# EEG_ECG.net
KiCad netlist of a schematic drawn in Altium Designer
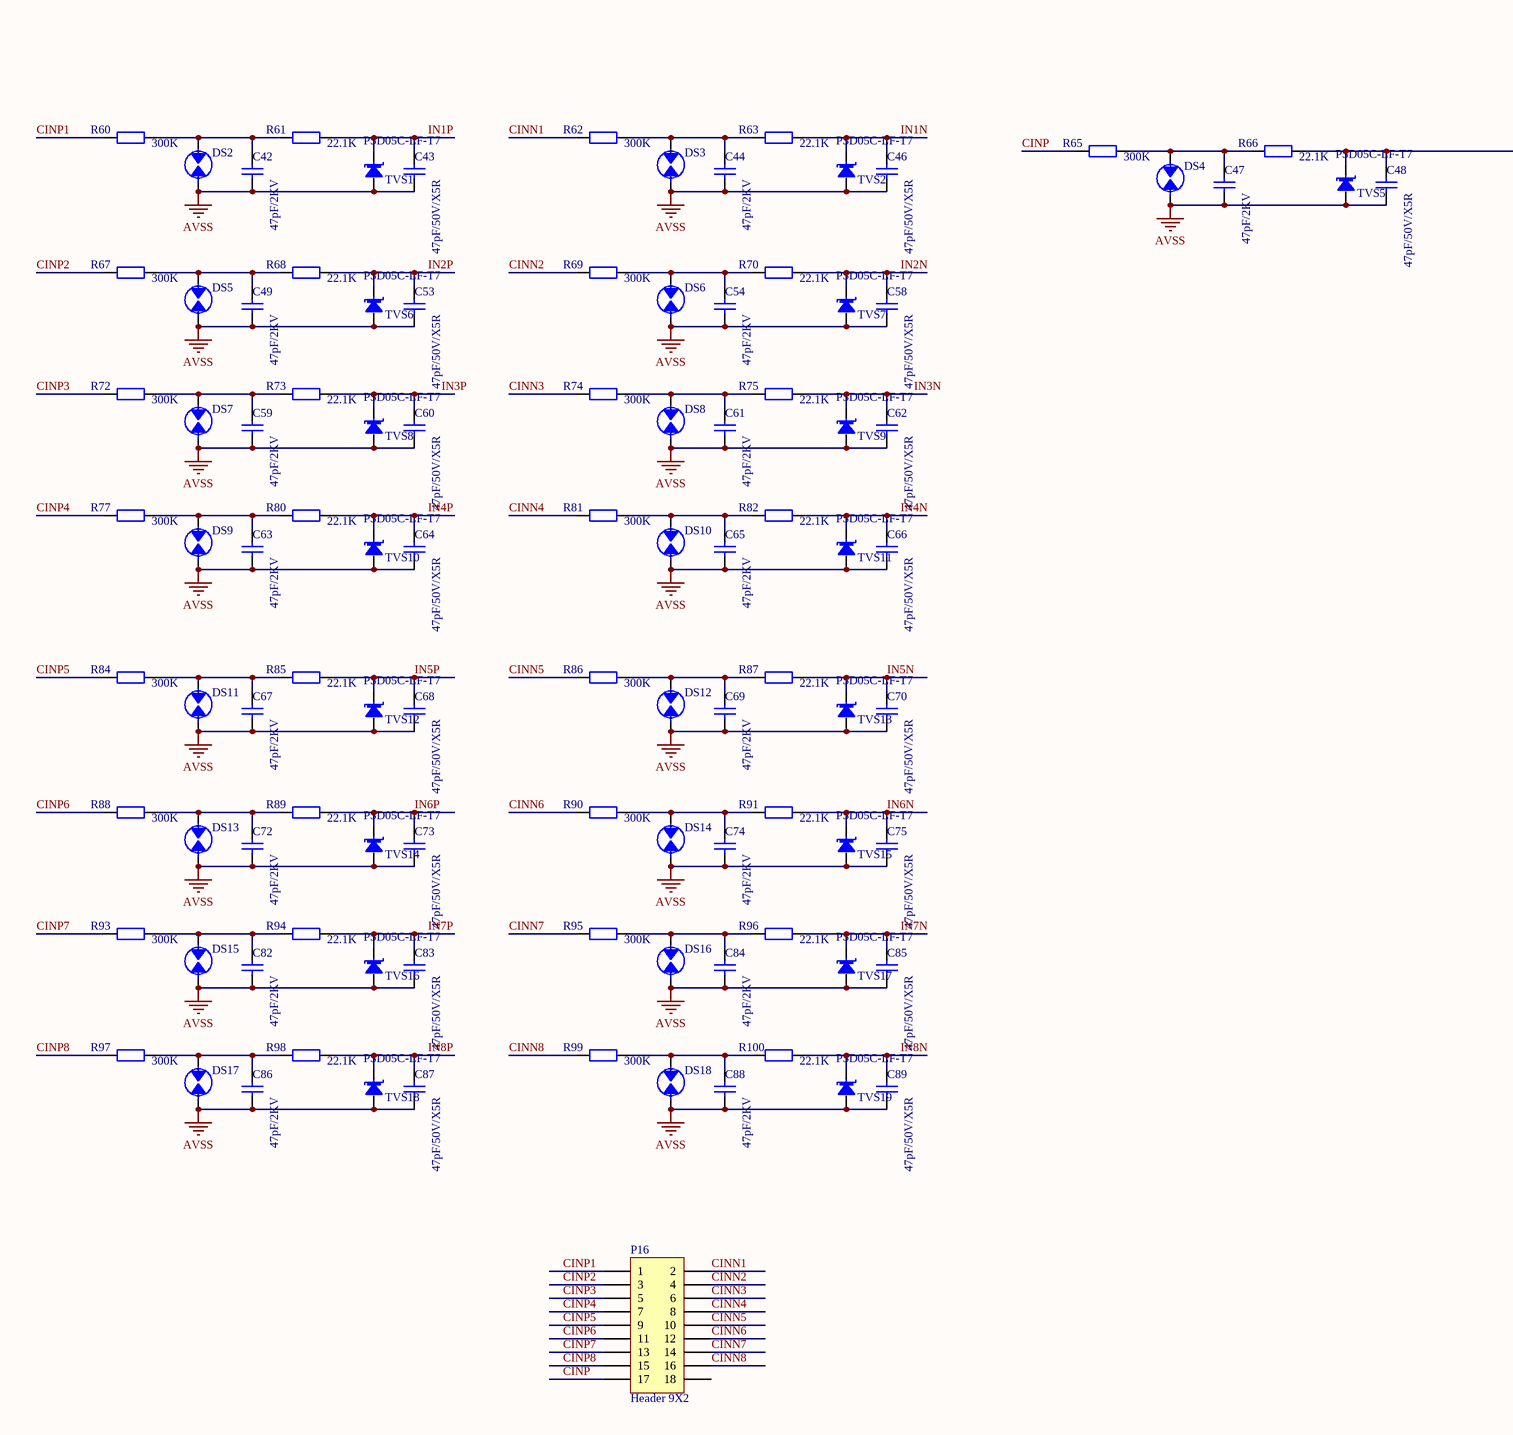
[diagram p0: EEG&ECG.SchDoc, top left]
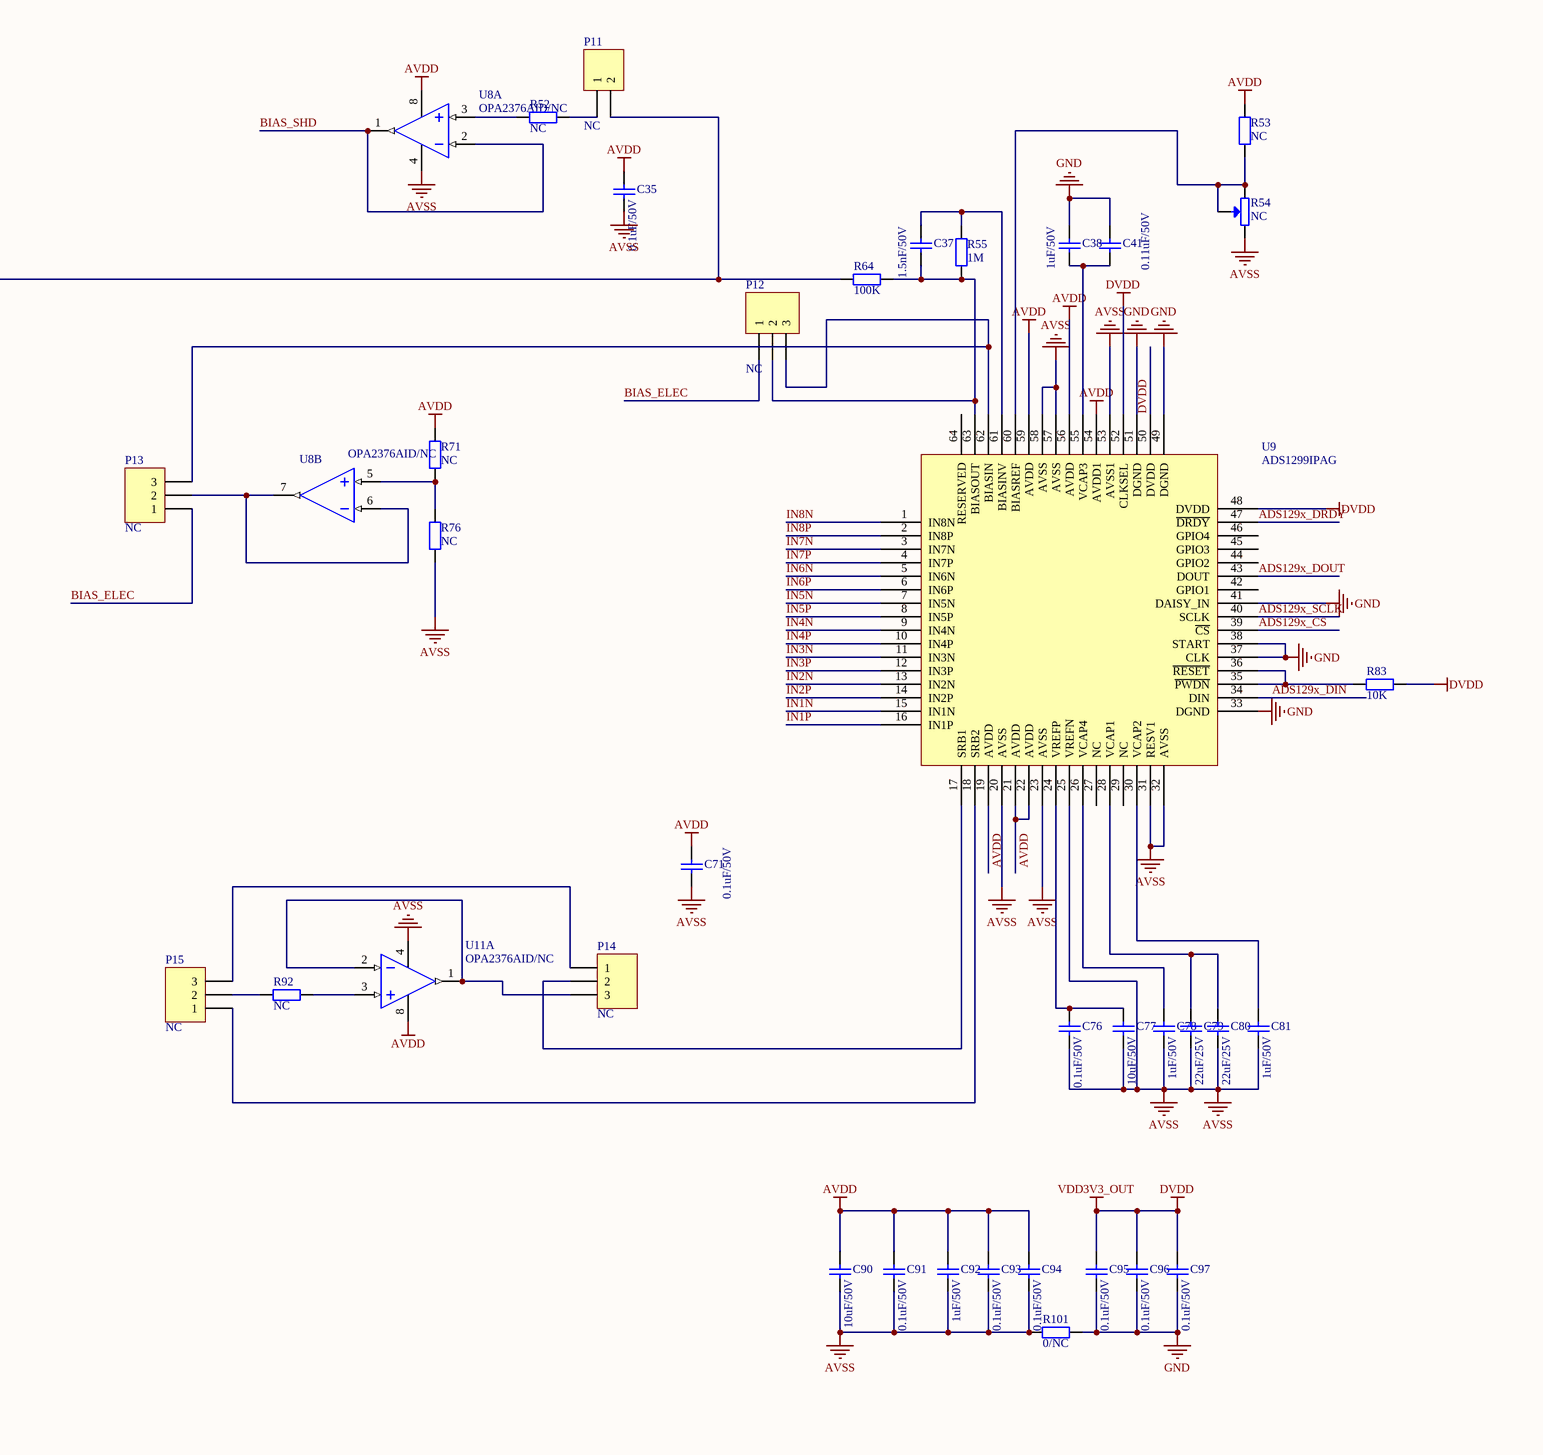
[diagram p1: EEG&ECG.SchDoc, top right]
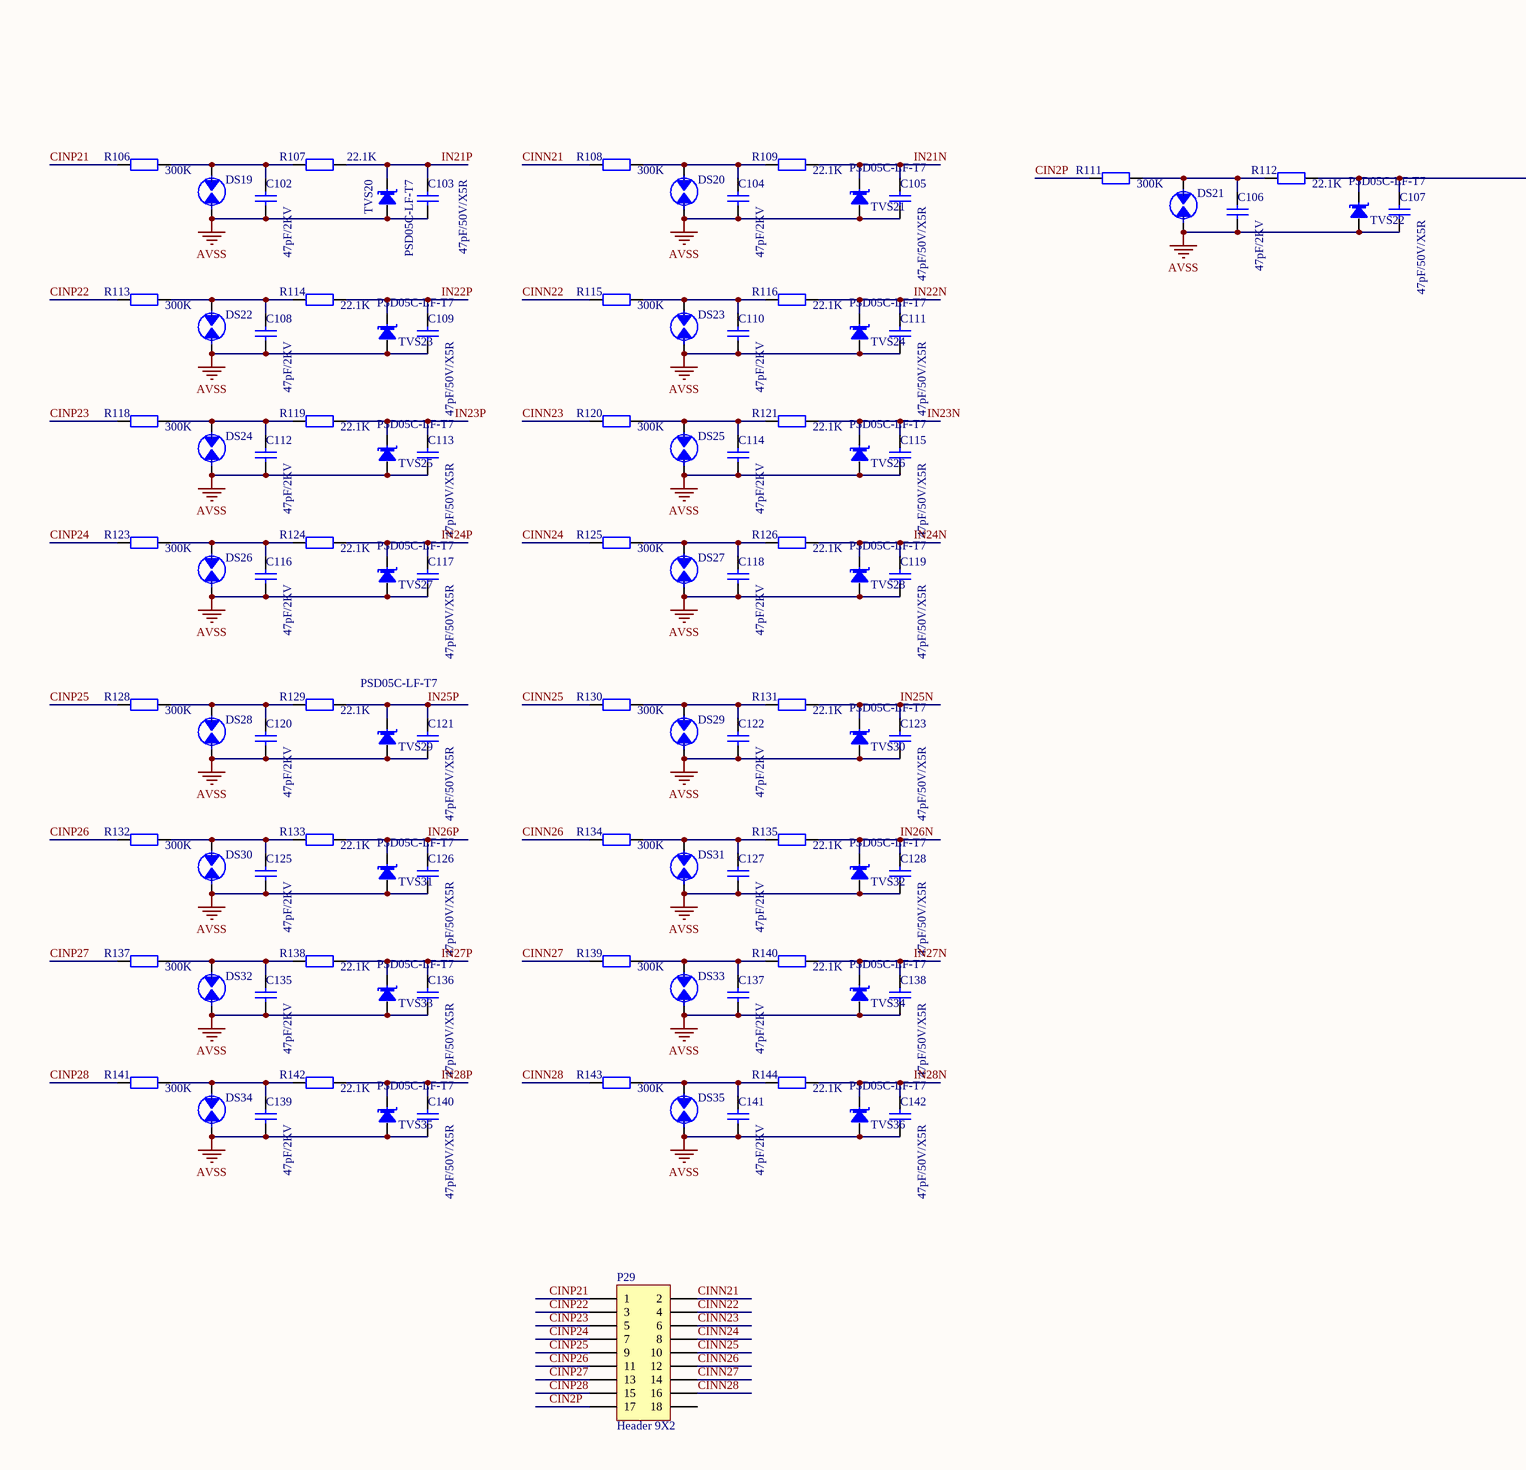
[diagram p2: EEG&ECG.SchDoc, bottom left]
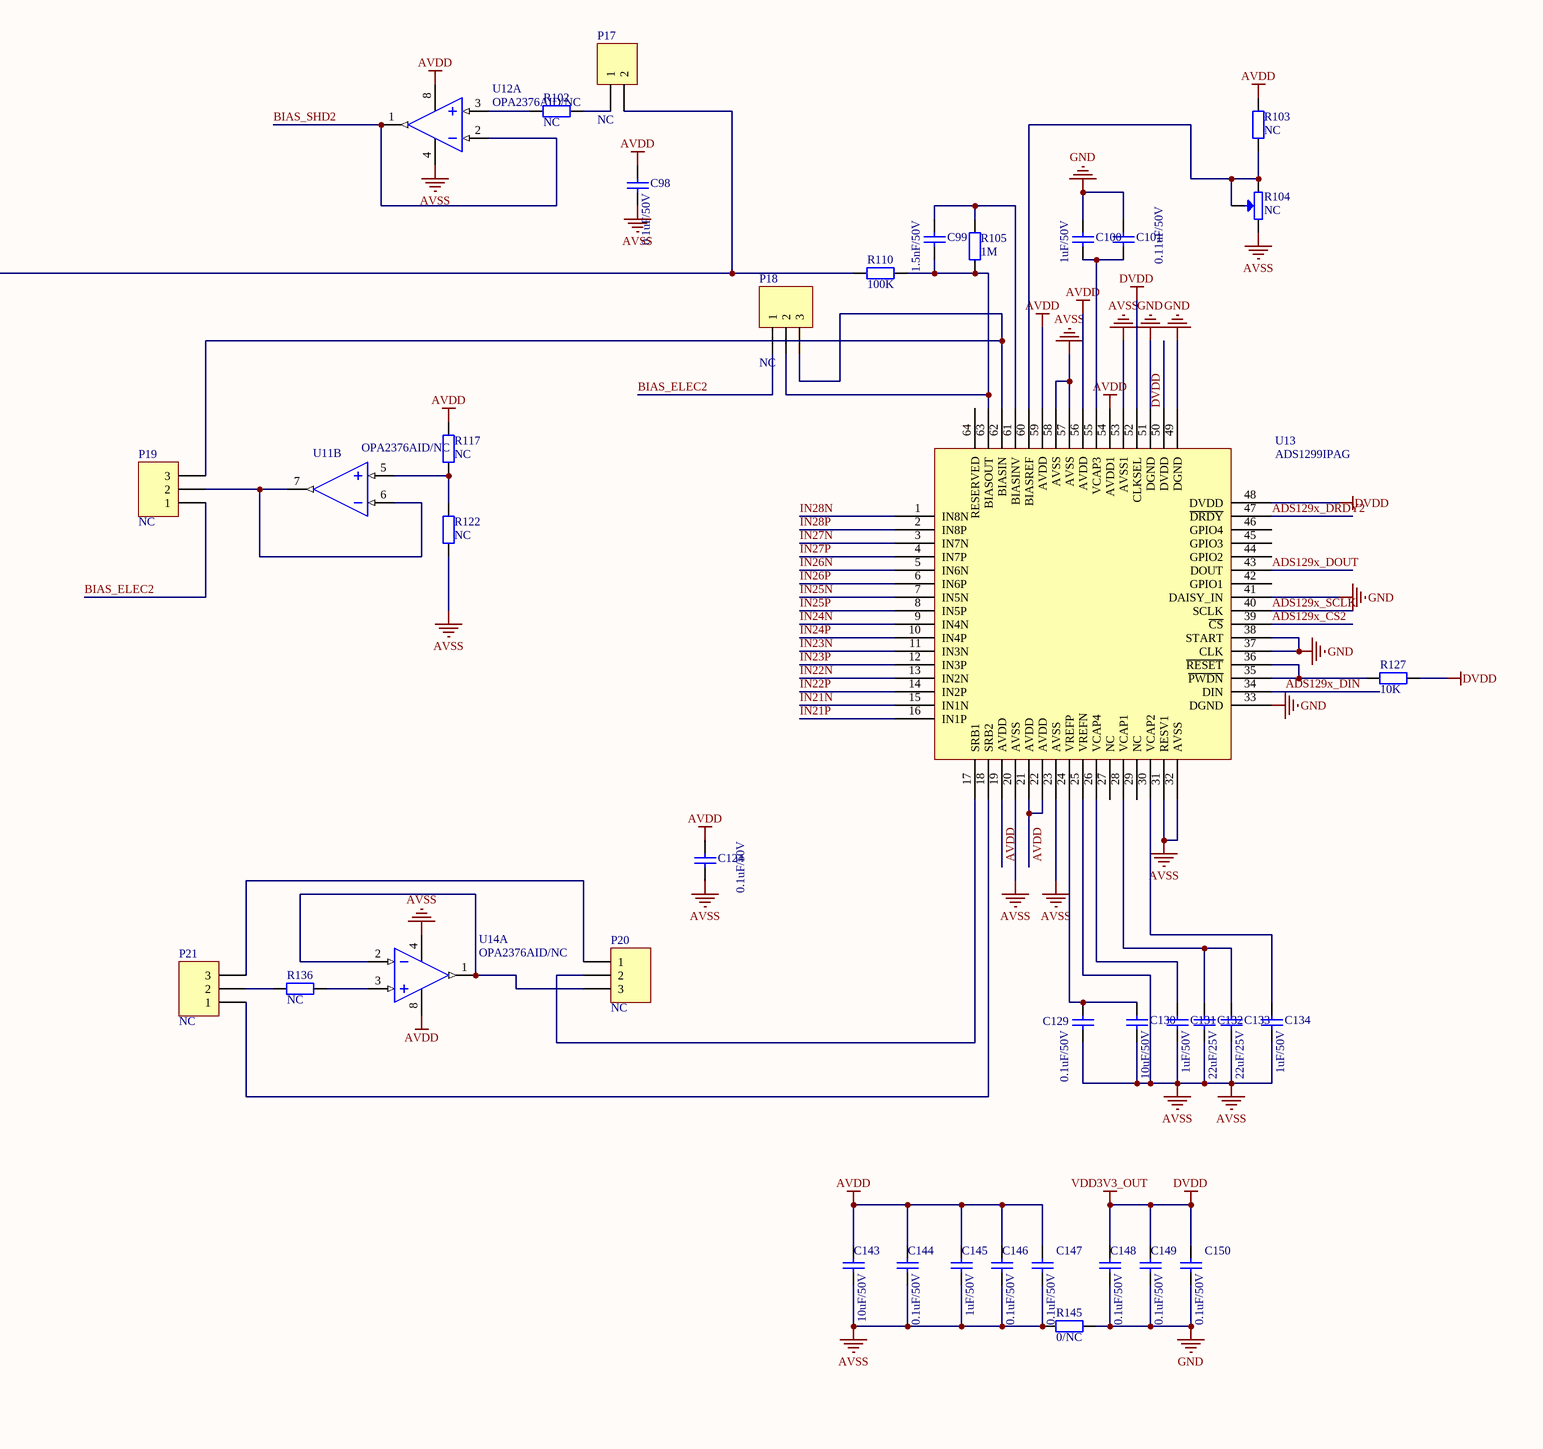
[diagram p3: EEG&ECG.SchDoc, bottom right]

(export (version "E")
  (design (tool "Eeschema 10.0.6"))
  (components
    (comp (ref "C35")
      (value "0.1uF/50V")
      (footprint "SMD-0603C")
      (description "贴片电容 20%")
      (libsource (lib "XiaoyI") (part "CAP4"))
    )
    (comp (ref "C37")
      (value "1.5nF/50V")
      (footprint "SMD-0603C")
      (description "贴片电容 20%")
      (libsource (lib "XiaoyI") (part "CAP4"))
    )
    (comp (ref "C38")
      (value "1uF/50V")
      (footprint "SMD-0603C")
      (description "贴片电容 20%")
      (libsource (lib "XiaoyI") (part "CAP4"))
    )
    (comp (ref "C41")
      (value "0.11uF/50V")
      (footprint "SMD-0603C")
      (description "贴片电容 20%")
      (libsource (lib "XiaoyI") (part "CAP4"))
    )
    (comp (ref "C42")
      (value "47pF/2KV")
      (footprint "1206c")
      (description "贴片电容 10%")
      (libsource (lib "XiaoyI") (part "CAP4"))
    )
    (comp (ref "C43")
      (value "47pF/50V/X5R")
      (footprint "SMD-0603C")
      (description "贴片电容 10%")
      (libsource (lib "XiaoyI") (part "CAP4"))
    )
    (comp (ref "C44")
      (value "47pF/2KV")
      (footprint "1206c")
      (description "贴片电容 10%")
      (libsource (lib "XiaoyI") (part "CAP4"))
    )
    (comp (ref "C46")
      (value "47pF/50V/X5R")
      (footprint "SMD-0603C")
      (description "贴片电容 10%")
      (libsource (lib "XiaoyI") (part "CAP4"))
    )
    (comp (ref "C47")
      (value "47pF/2KV")
      (footprint "1206c")
      (description "贴片电容 10%")
      (libsource (lib "XiaoyI") (part "CAP4"))
    )
    (comp (ref "C48")
      (value "47pF/50V/X5R")
      (footprint "SMD-0603C")
      (description "贴片电容 10%")
      (libsource (lib "XiaoyI") (part "CAP4"))
    )
    (comp (ref "C49")
      (value "47pF/2KV")
      (footprint "1206c")
      (description "贴片电容 10%")
      (libsource (lib "XiaoyI") (part "CAP4"))
    )
    (comp (ref "C53")
      (value "47pF/50V/X5R")
      (footprint "SMD-0603C")
      (description "贴片电容 10%")
      (libsource (lib "XiaoyI") (part "CAP4"))
    )
    (comp (ref "C54")
      (value "47pF/2KV")
      (footprint "1206c")
      (description "贴片电容 10%")
      (libsource (lib "XiaoyI") (part "CAP4"))
    )
    (comp (ref "C58")
      (value "47pF/50V/X5R")
      (footprint "SMD-0603C")
      (description "贴片电容 10%")
      (libsource (lib "XiaoyI") (part "CAP4"))
    )
    (comp (ref "C59")
      (value "47pF/2KV")
      (footprint "1206c")
      (description "贴片电容 10%")
      (libsource (lib "XiaoyI") (part "CAP4"))
    )
    (comp (ref "C60")
      (value "47pF/50V/X5R")
      (footprint "SMD-0603C")
      (description "贴片电容 10%")
      (libsource (lib "XiaoyI") (part "CAP4"))
    )
    (comp (ref "C61")
      (value "47pF/2KV")
      (footprint "1206c")
      (description "贴片电容 10%")
      (libsource (lib "XiaoyI") (part "CAP4"))
    )
    (comp (ref "C62")
      (value "47pF/50V/X5R")
      (footprint "SMD-0603C")
      (description "贴片电容 10%")
      (libsource (lib "XiaoyI") (part "CAP4"))
    )
    (comp (ref "C63")
      (value "47pF/2KV")
      (footprint "1206c")
      (description "贴片电容 10%")
      (libsource (lib "XiaoyI") (part "CAP4"))
    )
    (comp (ref "C64")
      (value "47pF/50V/X5R")
      (footprint "SMD-0603C")
      (description "贴片电容 10%")
      (libsource (lib "XiaoyI") (part "CAP4"))
    )
    (comp (ref "C65")
      (value "47pF/2KV")
      (footprint "1206c")
      (description "贴片电容 10%")
      (libsource (lib "XiaoyI") (part "CAP4"))
    )
    (comp (ref "C66")
      (value "47pF/50V/X5R")
      (footprint "SMD-0603C")
      (description "贴片电容 10%")
      (libsource (lib "XiaoyI") (part "CAP4"))
    )
    (comp (ref "C67")
      (value "47pF/2KV")
      (footprint "1206c")
      (description "贴片电容 10%")
      (libsource (lib "XiaoyI") (part "CAP4"))
    )
    (comp (ref "C68")
      (value "47pF/50V/X5R")
      (footprint "SMD-0603C")
      (description "贴片电容 10%")
      (libsource (lib "XiaoyI") (part "CAP4"))
    )
    (comp (ref "C69")
      (value "47pF/2KV")
      (footprint "1206c")
      (description "贴片电容 10%")
      (libsource (lib "XiaoyI") (part "CAP4"))
    )
    (comp (ref "C70")
      (value "47pF/50V/X5R")
      (footprint "SMD-0603C")
      (description "贴片电容 10%")
      (libsource (lib "XiaoyI") (part "CAP4"))
    )
    (comp (ref "C71")
      (value "0.1uF/50V")
      (footprint "SMD-0603C")
      (description "贴片电容 20%")
      (libsource (lib "XiaoyI") (part "CAP4"))
    )
    (comp (ref "C72")
      (value "47pF/2KV")
      (footprint "1206c")
      (description "贴片电容 10%")
      (libsource (lib "XiaoyI") (part "CAP4"))
    )
    (comp (ref "C73")
      (value "47pF/50V/X5R")
      (footprint "SMD-0603C")
      (description "贴片电容 10%")
      (libsource (lib "XiaoyI") (part "CAP4"))
    )
    (comp (ref "C74")
      (value "47pF/2KV")
      (footprint "1206c")
      (description "贴片电容 10%")
      (libsource (lib "XiaoyI") (part "CAP4"))
    )
    (comp (ref "C75")
      (value "47pF/50V/X5R")
      (footprint "SMD-0603C")
      (description "贴片电容 10%")
      (libsource (lib "XiaoyI") (part "CAP4"))
    )
    (comp (ref "C76")
      (value "0.1uF/50V")
      (footprint "SMD-0603C")
      (description "贴片电容 20%")
      (libsource (lib "XiaoyI") (part "CAP4"))
    )
    (comp (ref "C77")
      (value "10uF/50V")
      (footprint "SMD-0805C")
      (description "贴片电容 20%")
      (libsource (lib "XiaoyI") (part "CAP4"))
    )
    (comp (ref "C78")
      (value "1uF/50V")
      (footprint "SMD-0603C")
      (description "贴片电容 20%")
      (libsource (lib "XiaoyI") (part "CAP4"))
    )
    (comp (ref "C79")
      (value "22uF/25V")
      (footprint "SMD-0805C")
      (description "贴片电容 20%")
      (libsource (lib "XiaoyI") (part "CAP4"))
    )
    (comp (ref "C80")
      (value "22uF/25V")
      (footprint "SMD-0805C")
      (description "贴片电容 20%")
      (libsource (lib "XiaoyI") (part "CAP4"))
    )
    (comp (ref "C81")
      (value "1uF/50V")
      (footprint "SMD-0603C")
      (description "贴片电容 20%")
      (libsource (lib "XiaoyI") (part "CAP4"))
    )
    (comp (ref "C82")
      (value "47pF/2KV")
      (footprint "1206c")
      (description "贴片电容 10%")
      (libsource (lib "XiaoyI") (part "CAP4"))
    )
    (comp (ref "C83")
      (value "47pF/50V/X5R")
      (footprint "SMD-0603C")
      (description "贴片电容 10%")
      (libsource (lib "XiaoyI") (part "CAP4"))
    )
    (comp (ref "C84")
      (value "47pF/2KV")
      (footprint "1206c")
      (description "贴片电容 10%")
      (libsource (lib "XiaoyI") (part "CAP4"))
    )
    (comp (ref "C85")
      (value "47pF/50V/X5R")
      (footprint "SMD-0603C")
      (description "贴片电容 10%")
      (libsource (lib "XiaoyI") (part "CAP4"))
    )
    (comp (ref "C86")
      (value "47pF/2KV")
      (footprint "1206c")
      (description "贴片电容 10%")
      (libsource (lib "XiaoyI") (part "CAP4"))
    )
    (comp (ref "C87")
      (value "47pF/50V/X5R")
      (footprint "SMD-0603C")
      (description "贴片电容 10%")
      (libsource (lib "XiaoyI") (part "CAP4"))
    )
    (comp (ref "C88")
      (value "47pF/2KV")
      (footprint "1206c")
      (description "贴片电容 10%")
      (libsource (lib "XiaoyI") (part "CAP4"))
    )
    (comp (ref "C89")
      (value "47pF/50V/X5R")
      (footprint "SMD-0603C")
      (description "贴片电容 10%")
      (libsource (lib "XiaoyI") (part "CAP4"))
    )
    (comp (ref "C90")
      (value "10uF/50V")
      (footprint "SMD-0805C")
      (description "贴片电容 20%")
      (libsource (lib "XiaoyI") (part "CAP4"))
    )
    (comp (ref "C91")
      (value "0.1uF/50V")
      (footprint "SMD-0603C")
      (description "贴片电容 20%")
      (libsource (lib "XiaoyI") (part "CAP4"))
    )
    (comp (ref "C92")
      (value "1uF/50V")
      (footprint "SMD-0603C")
      (description "贴片电容 20%")
      (libsource (lib "XiaoyI") (part "CAP4"))
    )
    (comp (ref "C93")
      (value "0.1uF/50V")
      (footprint "SMD-0603C")
      (description "贴片电容 20%")
      (libsource (lib "XiaoyI") (part "CAP4"))
    )
    (comp (ref "C94")
      (value "0.1uF/50V")
      (footprint "SMD-0603C")
      (description "贴片电容 20%")
      (libsource (lib "XiaoyI") (part "CAP4"))
    )
    (comp (ref "C95")
      (value "0.1uF/50V")
      (footprint "SMD-0603C")
      (description "贴片电容 20%")
      (libsource (lib "XiaoyI") (part "CAP4"))
    )
    (comp (ref "C96")
      (value "0.1uF/50V")
      (footprint "SMD-0603C")
      (description "贴片电容 20%")
      (libsource (lib "XiaoyI") (part "CAP4"))
    )
    (comp (ref "C97")
      (value "0.1uF/50V")
      (footprint "SMD-0603C")
      (description "贴片电容 20%")
      (libsource (lib "XiaoyI") (part "CAP4"))
    )
    (comp (ref "C98")
      (value "0.1uF/50V")
      (footprint "SMD-0603C")
      (description "贴片电容 20%")
      (libsource (lib "XiaoyI") (part "CAP4"))
    )
    (comp (ref "C99")
      (value "1.5nF/50V")
      (footprint "SMD-0603C")
      (description "贴片电容 20%")
      (libsource (lib "XiaoyI") (part "CAP4"))
    )
    (comp (ref "C100")
      (value "1uF/50V")
      (footprint "SMD-0603C")
      (description "贴片电容 20%")
      (libsource (lib "XiaoyI") (part "CAP4"))
    )
    (comp (ref "C101")
      (value "0.11uF/50V")
      (footprint "SMD-0603C")
      (description "贴片电容 20%")
      (libsource (lib "XiaoyI") (part "CAP4"))
    )
    (comp (ref "C102")
      (value "47pF/2KV")
      (footprint "1206c")
      (description "贴片电容 10%")
      (libsource (lib "XiaoyI") (part "CAP4"))
    )
    (comp (ref "C103")
      (value "47pF/50V/X5R")
      (footprint "SMD-0603C")
      (description "贴片电容 10%")
      (libsource (lib "XiaoyI") (part "CAP4"))
    )
    (comp (ref "C104")
      (value "47pF/2KV")
      (footprint "1206c")
      (description "贴片电容 10%")
      (libsource (lib "XiaoyI") (part "CAP4"))
    )
    (comp (ref "C105")
      (value "47pF/50V/X5R")
      (footprint "SMD-0603C")
      (description "贴片电容 10%")
      (libsource (lib "XiaoyI") (part "CAP4"))
    )
    (comp (ref "C106")
      (value "47pF/2KV")
      (footprint "1206c")
      (description "贴片电容 10%")
      (libsource (lib "XiaoyI") (part "CAP4"))
    )
    (comp (ref "C107")
      (value "47pF/50V/X5R")
      (footprint "SMD-0603C")
      (description "贴片电容 10%")
      (libsource (lib "XiaoyI") (part "CAP4"))
    )
    (comp (ref "C108")
      (value "47pF/2KV")
      (footprint "1206c")
      (description "贴片电容 10%")
      (libsource (lib "XiaoyI") (part "CAP4"))
    )
    (comp (ref "C109")
      (value "47pF/50V/X5R")
      (footprint "SMD-0603C")
      (description "贴片电容 10%")
      (libsource (lib "XiaoyI") (part "CAP4"))
    )
    (comp (ref "C110")
      (value "47pF/2KV")
      (footprint "1206c")
      (description "贴片电容 10%")
      (libsource (lib "XiaoyI") (part "CAP4"))
    )
    (comp (ref "C111")
      (value "47pF/50V/X5R")
      (footprint "SMD-0603C")
      (description "贴片电容 10%")
      (libsource (lib "XiaoyI") (part "CAP4"))
    )
    (comp (ref "C112")
      (value "47pF/2KV")
      (footprint "1206c")
      (description "贴片电容 10%")
      (libsource (lib "XiaoyI") (part "CAP4"))
    )
    (comp (ref "C113")
      (value "47pF/50V/X5R")
      (footprint "SMD-0603C")
      (description "贴片电容 10%")
      (libsource (lib "XiaoyI") (part "CAP4"))
    )
    (comp (ref "C114")
      (value "47pF/2KV")
      (footprint "1206c")
      (description "贴片电容 10%")
      (libsource (lib "XiaoyI") (part "CAP4"))
    )
    (comp (ref "C115")
      (value "47pF/50V/X5R")
      (footprint "SMD-0603C")
      (description "贴片电容 10%")
      (libsource (lib "XiaoyI") (part "CAP4"))
    )
    (comp (ref "C116")
      (value "47pF/2KV")
      (footprint "1206c")
      (description "贴片电容 10%")
      (libsource (lib "XiaoyI") (part "CAP4"))
    )
    (comp (ref "C117")
      (value "47pF/50V/X5R")
      (footprint "SMD-0603C")
      (description "贴片电容 10%")
      (libsource (lib "XiaoyI") (part "CAP4"))
    )
    (comp (ref "C118")
      (value "47pF/2KV")
      (footprint "1206c")
      (description "贴片电容 10%")
      (libsource (lib "XiaoyI") (part "CAP4"))
    )
    (comp (ref "C119")
      (value "47pF/50V/X5R")
      (footprint "SMD-0603C")
      (description "贴片电容 10%")
      (libsource (lib "XiaoyI") (part "CAP4"))
    )
    (comp (ref "C120")
      (value "47pF/2KV")
      (footprint "1206c")
      (description "贴片电容 10%")
      (libsource (lib "XiaoyI") (part "CAP4"))
    )
    (comp (ref "C121")
      (value "47pF/50V/X5R")
      (footprint "SMD-0603C")
      (description "贴片电容 10%")
      (libsource (lib "XiaoyI") (part "CAP4"))
    )
    (comp (ref "C122")
      (value "47pF/2KV")
      (footprint "1206c")
      (description "贴片电容 10%")
      (libsource (lib "XiaoyI") (part "CAP4"))
    )
    (comp (ref "C123")
      (value "47pF/50V/X5R")
      (footprint "SMD-0603C")
      (description "贴片电容 10%")
      (libsource (lib "XiaoyI") (part "CAP4"))
    )
    (comp (ref "C124")
      (value "0.1uF/50V")
      (footprint "SMD-0603C")
      (description "贴片电容 20%")
      (libsource (lib "XiaoyI") (part "CAP4"))
    )
    (comp (ref "C125")
      (value "47pF/2KV")
      (footprint "1206c")
      (description "贴片电容 10%")
      (libsource (lib "XiaoyI") (part "CAP4"))
    )
    (comp (ref "C126")
      (value "47pF/50V/X5R")
      (footprint "SMD-0603C")
      (description "贴片电容 10%")
      (libsource (lib "XiaoyI") (part "CAP4"))
    )
    (comp (ref "C127")
      (value "47pF/2KV")
      (footprint "1206c")
      (description "贴片电容 10%")
      (libsource (lib "XiaoyI") (part "CAP4"))
    )
    (comp (ref "C128")
      (value "47pF/50V/X5R")
      (footprint "SMD-0603C")
      (description "贴片电容 10%")
      (libsource (lib "XiaoyI") (part "CAP4"))
    )
    (comp (ref "C129")
      (value "0.1uF/50V")
      (footprint "SMD-0603C")
      (description "贴片电容 20%")
      (libsource (lib "XiaoyI") (part "CAP4"))
    )
    (comp (ref "C130")
      (value "10uF/50V")
      (footprint "SMD-0805C")
      (description "贴片电容 20%")
      (libsource (lib "XiaoyI") (part "CAP4"))
    )
    (comp (ref "C131")
      (value "1uF/50V")
      (footprint "SMD-0603C")
      (description "贴片电容 20%")
      (libsource (lib "XiaoyI") (part "CAP4"))
    )
    (comp (ref "C132")
      (value "22uF/25V")
      (footprint "SMD-0805C")
      (description "贴片电容 20%")
      (libsource (lib "XiaoyI") (part "CAP4"))
    )
    (comp (ref "C133")
      (value "22uF/25V")
      (footprint "SMD-0805C")
      (description "贴片电容 20%")
      (libsource (lib "XiaoyI") (part "CAP4"))
    )
    (comp (ref "C134")
      (value "1uF/50V")
      (footprint "SMD-0603C")
      (description "贴片电容 20%")
      (libsource (lib "XiaoyI") (part "CAP4"))
    )
    (comp (ref "C135")
      (value "47pF/2KV")
      (footprint "1206c")
      (description "贴片电容 10%")
      (libsource (lib "XiaoyI") (part "CAP4"))
    )
    (comp (ref "C136")
      (value "47pF/50V/X5R")
      (footprint "SMD-0603C")
      (description "贴片电容 10%")
      (libsource (lib "XiaoyI") (part "CAP4"))
    )
    (comp (ref "C137")
      (value "47pF/2KV")
      (footprint "1206c")
      (description "贴片电容 10%")
      (libsource (lib "XiaoyI") (part "CAP4"))
    )
    (comp (ref "C138")
      (value "47pF/50V/X5R")
      (footprint "SMD-0603C")
      (description "贴片电容 10%")
      (libsource (lib "XiaoyI") (part "CAP4"))
    )
    (comp (ref "C139")
      (value "47pF/2KV")
      (footprint "1206c")
      (description "贴片电容 10%")
      (libsource (lib "XiaoyI") (part "CAP4"))
    )
    (comp (ref "C140")
      (value "47pF/50V/X5R")
      (footprint "SMD-0603C")
      (description "贴片电容 10%")
      (libsource (lib "XiaoyI") (part "CAP4"))
    )
    (comp (ref "C141")
      (value "47pF/2KV")
      (footprint "1206c")
      (description "贴片电容 10%")
      (libsource (lib "XiaoyI") (part "CAP4"))
    )
    (comp (ref "C142")
      (value "47pF/50V/X5R")
      (footprint "SMD-0603C")
      (description "贴片电容 10%")
      (libsource (lib "XiaoyI") (part "CAP4"))
    )
    (comp (ref "C143")
      (value "10uF/50V")
      (footprint "SMD-0805C")
      (description "贴片电容 20%")
      (libsource (lib "XiaoyI") (part "CAP4"))
    )
    (comp (ref "C144")
      (value "0.1uF/50V")
      (footprint "SMD-0603C")
      (description "贴片电容 20%")
      (libsource (lib "XiaoyI") (part "CAP4"))
    )
    (comp (ref "C145")
      (value "1uF/50V")
      (footprint "SMD-0603C")
      (description "贴片电容 20%")
      (libsource (lib "XiaoyI") (part "CAP4"))
    )
    (comp (ref "C146")
      (value "0.1uF/50V")
      (footprint "SMD-0603C")
      (description "贴片电容 20%")
      (libsource (lib "XiaoyI") (part "CAP4"))
    )
    (comp (ref "C147")
      (value "0.1uF/50V")
      (footprint "SMD-0603C")
      (description "贴片电容 20%")
      (libsource (lib "XiaoyI") (part "CAP4"))
    )
    (comp (ref "C148")
      (value "0.1uF/50V")
      (footprint "SMD-0603C")
      (description "贴片电容 20%")
      (libsource (lib "XiaoyI") (part "CAP4"))
    )
    (comp (ref "C149")
      (value "0.1uF/50V")
      (footprint "SMD-0603C")
      (description "贴片电容 20%")
      (libsource (lib "XiaoyI") (part "CAP4"))
    )
    (comp (ref "C150")
      (value "0.1uF/50V")
      (footprint "SMD-0603C")
      (description "贴片电容 20%")
      (libsource (lib "XiaoyI") (part "CAP4"))
    )
    (comp (ref "DS2")
      (value "UN1812-90CSMD")
      (footprint "SMD-1812")
      (description "气体放电管 90V")
      (libsource (lib "ABB") (part "DISCHARE-1"))
    )
    (comp (ref "DS3")
      (value "UN1812-90CSMD")
      (footprint "SMD-1812")
      (description "气体放电管 90V")
      (libsource (lib "ABB") (part "DISCHARE-1"))
    )
    (comp (ref "DS4")
      (value "UN1812-90CSMD")
      (footprint "SMD-1812")
      (description "气体放电管 90V")
      (libsource (lib "ABB") (part "DISCHARE-1"))
    )
    (comp (ref "DS5")
      (value "UN1812-90CSMD")
      (footprint "SMD-1812")
      (description "气体放电管 90V")
      (libsource (lib "ABB") (part "DISCHARE-1"))
    )
    (comp (ref "DS6")
      (value "UN1812-90CSMD")
      (footprint "SMD-1812")
      (description "气体放电管 90V")
      (libsource (lib "ABB") (part "DISCHARE-1"))
    )
    (comp (ref "DS7")
      (value "UN1812-90CSMD")
      (footprint "SMD-1812")
      (description "气体放电管 90V")
      (libsource (lib "ABB") (part "DISCHARE-1"))
    )
    (comp (ref "DS8")
      (value "UN1812-90CSMD")
      (footprint "SMD-1812")
      (description "气体放电管 90V")
      (libsource (lib "ABB") (part "DISCHARE-1"))
    )
    (comp (ref "DS9")
      (value "UN1812-90CSMD")
      (footprint "SMD-1812")
      (description "气体放电管 90V")
      (libsource (lib "ABB") (part "DISCHARE-1"))
    )
    (comp (ref "DS10")
      (value "UN1812-90CSMD")
      (footprint "SMD-1812")
      (description "气体放电管 90V")
      (libsource (lib "ABB") (part "DISCHARE-1"))
    )
    (comp (ref "DS11")
      (value "UN1812-90CSMD")
      (footprint "SMD-1812")
      (description "气体放电管 90V")
      (libsource (lib "ABB") (part "DISCHARE-1"))
    )
    (comp (ref "DS12")
      (value "UN1812-90CSMD")
      (footprint "SMD-1812")
      (description "气体放电管 90V")
      (libsource (lib "ABB") (part "DISCHARE-1"))
    )
    (comp (ref "DS13")
      (value "UN1812-90CSMD")
      (footprint "SMD-1812")
      (description "气体放电管 90V")
      (libsource (lib "ABB") (part "DISCHARE-1"))
    )
    (comp (ref "DS14")
      (value "UN1812-90CSMD")
      (footprint "SMD-1812")
      (description "气体放电管 90V")
      (libsource (lib "ABB") (part "DISCHARE-1"))
    )
    (comp (ref "DS15")
      (value "UN1812-90CSMD")
      (footprint "SMD-1812")
      (description "气体放电管 90V")
      (libsource (lib "ABB") (part "DISCHARE-1"))
    )
    (comp (ref "DS16")
      (value "UN1812-90CSMD")
      (footprint "SMD-1812")
      (description "气体放电管 90V")
      (libsource (lib "ABB") (part "DISCHARE-1"))
    )
    (comp (ref "DS17")
      (value "UN1812-90CSMD")
      (footprint "SMD-1812")
      (description "气体放电管 90V")
      (libsource (lib "ABB") (part "DISCHARE-1"))
    )
    (comp (ref "DS18")
      (value "UN1812-90CSMD")
      (footprint "SMD-1812")
      (description "气体放电管 90V")
      (libsource (lib "ABB") (part "DISCHARE-1"))
    )
    (comp (ref "DS19")
      (value "UN1812-90CSMD")
      (footprint "SMD-1812")
      (description "气体放电管 90V")
      (libsource (lib "ABB") (part "DISCHARE-1"))
    )
    (comp (ref "DS20")
      (value "UN1812-90CSMD")
      (footprint "SMD-1812")
      (description "气体放电管 90V")
      (libsource (lib "ABB") (part "DISCHARE-1"))
    )
    (comp (ref "DS21")
      (value "UN1812-90CSMD")
      (footprint "SMD-1812")
      (description "气体放电管 90V")
      (libsource (lib "ABB") (part "DISCHARE-1"))
    )
    (comp (ref "DS22")
      (value "UN1812-90CSMD")
      (footprint "SMD-1812")
      (description "气体放电管 90V")
      (libsource (lib "ABB") (part "DISCHARE-1"))
    )
    (comp (ref "DS23")
      (value "UN1812-90CSMD")
      (footprint "SMD-1812")
      (description "气体放电管 90V")
      (libsource (lib "ABB") (part "DISCHARE-1"))
    )
    (comp (ref "DS24")
      (value "UN1812-90CSMD")
      (footprint "SMD-1812")
      (description "气体放电管 90V")
      (libsource (lib "ABB") (part "DISCHARE-1"))
    )
    (comp (ref "DS25")
      (value "UN1812-90CSMD")
      (footprint "SMD-1812")
      (description "气体放电管 90V")
      (libsource (lib "ABB") (part "DISCHARE-1"))
    )
    (comp (ref "DS26")
      (value "UN1812-90CSMD")
      (footprint "SMD-1812")
      (description "气体放电管 90V")
      (libsource (lib "ABB") (part "DISCHARE-1"))
    )
    (comp (ref "DS27")
      (value "UN1812-90CSMD")
      (footprint "SMD-1812")
      (description "气体放电管 90V")
      (libsource (lib "ABB") (part "DISCHARE-1"))
    )
    (comp (ref "DS28")
      (value "UN1812-90CSMD")
      (footprint "SMD-1812")
      (description "气体放电管 90V")
      (libsource (lib "ABB") (part "DISCHARE-1"))
    )
    (comp (ref "DS29")
      (value "UN1812-90CSMD")
      (footprint "SMD-1812")
      (description "气体放电管 90V")
      (libsource (lib "ABB") (part "DISCHARE-1"))
    )
    (comp (ref "DS30")
      (value "UN1812-90CSMD")
      (footprint "SMD-1812")
      (description "气体放电管 90V")
      (libsource (lib "ABB") (part "DISCHARE-1"))
    )
    (comp (ref "DS31")
      (value "UN1812-90CSMD")
      (footprint "SMD-1812")
      (description "气体放电管 90V")
      (libsource (lib "ABB") (part "DISCHARE-1"))
    )
    (comp (ref "DS32")
      (value "UN1812-90CSMD")
      (footprint "SMD-1812")
      (description "气体放电管 90V")
      (libsource (lib "ABB") (part "DISCHARE-1"))
    )
    (comp (ref "DS33")
      (value "UN1812-90CSMD")
      (footprint "SMD-1812")
      (description "气体放电管 90V")
      (libsource (lib "ABB") (part "DISCHARE-1"))
    )
    (comp (ref "DS34")
      (value "UN1812-90CSMD")
      (footprint "SMD-1812")
      (description "气体放电管 90V")
      (libsource (lib "ABB") (part "DISCHARE-1"))
    )
    (comp (ref "DS35")
      (value "UN1812-90CSMD")
      (footprint "SMD-1812")
      (description "气体放电管 90V")
      (libsource (lib "ABB") (part "DISCHARE-1"))
    )
    (comp (ref "P11")
      (value "NC")
      (footprint "HDR1X2")
      (description "Header, 2-Pin")
      (fields (field (name "PUBLISHER") "Altium Limited"))
      (libsource (lib "Miscellaneous Connectors") (part "Header 2"))
    )
    (comp (ref "P12")
      (value "NC")
      (footprint "HDR1X3")
      (description "Header, 3-Pin")
      (fields (field (name "PUBLISHER") "Altium Limited"))
      (libsource (lib "") (part "Header 3_2"))
    )
    (comp (ref "P13")
      (value "NC")
      (footprint "HDR1X3")
      (description "Header, 3-Pin")
      (fields (field (name "PUBLISHER") "Altium Limited"))
      (libsource (lib "Miscellaneous Connectors") (part "Header 3"))
    )
    (comp (ref "P14")
      (value "NC")
      (footprint "HDR1X3")
      (description "Header, 3-Pin")
      (fields (field (name "PUBLISHER") "Altium Limited"))
      (libsource (lib "") (part "Header 3_1"))
    )
    (comp (ref "P15")
      (value "NC")
      (footprint "HDR1X3")
      (description "Header, 3-Pin")
      (fields (field (name "PUBLISHER") "Altium Limited"))
      (libsource (lib "Miscellaneous Connectors") (part "Header 3"))
    )
    (comp (ref "P16")
      (value "Header 9X2")
      (footprint "HDR2X9")
      (description "Header, 9-Pin, Dual row")
      (fields (field (name "PUBLISHER") "Altium Limited"))
      (libsource (lib "Miscellaneous Connectors") (part "Header 9X2"))
    )
    (comp (ref "P17")
      (value "NC")
      (footprint "HDR1X2")
      (description "Header, 2-Pin")
      (fields (field (name "PUBLISHER") "Altium Limited"))
      (libsource (lib "Miscellaneous Connectors") (part "Header 2"))
    )
    (comp (ref "P18")
      (value "NC")
      (footprint "HDR1X3")
      (description "Header, 3-Pin")
      (fields (field (name "PUBLISHER") "Altium Limited"))
      (libsource (lib "") (part "Header 3_2"))
    )
    (comp (ref "P19")
      (value "NC")
      (footprint "HDR1X3")
      (description "Header, 3-Pin")
      (fields (field (name "PUBLISHER") "Altium Limited"))
      (libsource (lib "Miscellaneous Connectors") (part "Header 3"))
    )
    (comp (ref "P20")
      (value "NC")
      (footprint "HDR1X3")
      (description "Header, 3-Pin")
      (fields (field (name "PUBLISHER") "Altium Limited"))
      (libsource (lib "") (part "Header 3_1"))
    )
    (comp (ref "P21")
      (value "NC")
      (footprint "HDR1X3")
      (description "Header, 3-Pin")
      (fields (field (name "PUBLISHER") "Altium Limited"))
      (libsource (lib "Miscellaneous Connectors") (part "Header 3"))
    )
    (comp (ref "P29")
      (value "Header 9X2")
      (footprint "HDR2X9")
      (description "Header, 9-Pin, Dual row")
      (fields (field (name "PUBLISHER") "Altium Limited"))
      (libsource (lib "Miscellaneous Connectors") (part "Header 9X2"))
    )
    (comp (ref "R52")
      (value "NC")
      (footprint "SMD-0603")
      (description "贴片电阻 5%")
      (libsource (lib "XiaoyI") (part "RES2"))
    )
    (comp (ref "R53")
      (value "NC")
      (footprint "SMD-0603")
      (description "贴片电阻 5%")
      (libsource (lib "") (part "RES2_1"))
    )
    (comp (ref "R54")
      (value "NC")
      (footprint "VR-05")
      (description "可调电阻")
      (libsource (lib "ABB") (part "RES4"))
    )
    (comp (ref "R55")
      (value "1M")
      (footprint "SMD-0603")
      (description "贴片电阻 5%")
      (libsource (lib "") (part "RES2_1"))
    )
    (comp (ref "R60")
      (value "300K")
      (footprint "SMD-0603")
      (description "贴片电阻 1%")
      (libsource (lib "ABB") (part "RES0"))
    )
    (comp (ref "R61")
      (value "22.1K")
      (footprint "SMD-0603")
      (description "贴片电阻 1%")
      (libsource (lib "ABB") (part "RES0"))
    )
    (comp (ref "R62")
      (value "300K")
      (footprint "SMD-0603")
      (description "贴片电阻 1%")
      (libsource (lib "ABB") (part "RES0"))
    )
    (comp (ref "R63")
      (value "22.1K")
      (footprint "SMD-0603")
      (description "贴片电阻 1%")
      (libsource (lib "ABB") (part "RES0"))
    )
    (comp (ref "R64")
      (value "100K")
      (footprint "SMD-0603")
      (description "贴片电阻 5%")
      (libsource (lib "XiaoyI") (part "RES2"))
    )
    (comp (ref "R65")
      (value "300K")
      (footprint "SMD-0603")
      (description "贴片电阻 1%")
      (libsource (lib "ABB") (part "RES0"))
    )
    (comp (ref "R66")
      (value "22.1K")
      (footprint "SMD-0603")
      (description "贴片电阻 1%")
      (libsource (lib "ABB") (part "RES0"))
    )
    (comp (ref "R67")
      (value "300K")
      (footprint "SMD-0603")
      (description "贴片电阻 1%")
      (libsource (lib "ABB") (part "RES0"))
    )
    (comp (ref "R68")
      (value "22.1K")
      (footprint "SMD-0603")
      (description "贴片电阻 1%")
      (libsource (lib "ABB") (part "RES0"))
    )
    (comp (ref "R69")
      (value "300K")
      (footprint "SMD-0603")
      (description "贴片电阻 1%")
      (libsource (lib "ABB") (part "RES0"))
    )
    (comp (ref "R70")
      (value "22.1K")
      (footprint "SMD-0603")
      (description "贴片电阻 1%")
      (libsource (lib "ABB") (part "RES0"))
    )
    (comp (ref "R71")
      (value "NC")
      (footprint "SMD-0603")
      (description "贴片电阻 5%")
      (libsource (lib "") (part "RES2_1"))
    )
    (comp (ref "R72")
      (value "300K")
      (footprint "SMD-0603")
      (description "贴片电阻 1%")
      (libsource (lib "ABB") (part "RES0"))
    )
    (comp (ref "R73")
      (value "22.1K")
      (footprint "SMD-0603")
      (description "贴片电阻 1%")
      (libsource (lib "ABB") (part "RES0"))
    )
    (comp (ref "R74")
      (value "300K")
      (footprint "SMD-0603")
      (description "贴片电阻 1%")
      (libsource (lib "ABB") (part "RES0"))
    )
    (comp (ref "R75")
      (value "22.1K")
      (footprint "SMD-0603")
      (description "贴片电阻 1%")
      (libsource (lib "ABB") (part "RES0"))
    )
    (comp (ref "R76")
      (value "NC")
      (footprint "SMD-0603")
      (description "贴片电阻 5%")
      (libsource (lib "") (part "RES2_1"))
    )
    (comp (ref "R77")
      (value "300K")
      (footprint "SMD-0603")
      (description "贴片电阻 1%")
      (libsource (lib "ABB") (part "RES0"))
    )
    (comp (ref "R80")
      (value "22.1K")
      (footprint "SMD-0603")
      (description "贴片电阻 1%")
      (libsource (lib "ABB") (part "RES0"))
    )
    (comp (ref "R81")
      (value "300K")
      (footprint "SMD-0603")
      (description "贴片电阻 1%")
      (libsource (lib "ABB") (part "RES0"))
    )
    (comp (ref "R82")
      (value "22.1K")
      (footprint "SMD-0603")
      (description "贴片电阻 1%")
      (libsource (lib "ABB") (part "RES0"))
    )
    (comp (ref "R83")
      (value "10K")
      (footprint "SMD-0603")
      (description "贴片电阻 5%")
      (libsource (lib "XiaoyI") (part "RES2"))
    )
    (comp (ref "R84")
      (value "300K")
      (footprint "SMD-0603")
      (description "贴片电阻 1%")
      (libsource (lib "ABB") (part "RES0"))
    )
    (comp (ref "R85")
      (value "22.1K")
      (footprint "SMD-0603")
      (description "贴片电阻 1%")
      (libsource (lib "ABB") (part "RES0"))
    )
    (comp (ref "R86")
      (value "300K")
      (footprint "SMD-0603")
      (description "贴片电阻 1%")
      (libsource (lib "ABB") (part "RES0"))
    )
    (comp (ref "R87")
      (value "22.1K")
      (footprint "SMD-0603")
      (description "贴片电阻 1%")
      (libsource (lib "ABB") (part "RES0"))
    )
    (comp (ref "R88")
      (value "300K")
      (footprint "SMD-0603")
      (description "贴片电阻 1%")
      (libsource (lib "ABB") (part "RES0"))
    )
    (comp (ref "R89")
      (value "22.1K")
      (footprint "SMD-0603")
      (description "贴片电阻 1%")
      (libsource (lib "ABB") (part "RES0"))
    )
    (comp (ref "R90")
      (value "300K")
      (footprint "SMD-0603")
      (description "贴片电阻 1%")
      (libsource (lib "ABB") (part "RES0"))
    )
    (comp (ref "R91")
      (value "22.1K")
      (footprint "SMD-0603")
      (description "贴片电阻 1%")
      (libsource (lib "ABB") (part "RES0"))
    )
    (comp (ref "R92")
      (value "NC")
      (footprint "SMD-0603")
      (description "贴片电阻 5%")
      (libsource (lib "") (part "RES2_2"))
    )
    (comp (ref "R93")
      (value "300K")
      (footprint "SMD-0603")
      (description "贴片电阻 1%")
      (libsource (lib "ABB") (part "RES0"))
    )
    (comp (ref "R94")
      (value "22.1K")
      (footprint "SMD-0603")
      (description "贴片电阻 1%")
      (libsource (lib "ABB") (part "RES0"))
    )
    (comp (ref "R95")
      (value "300K")
      (footprint "SMD-0603")
      (description "贴片电阻 1%")
      (libsource (lib "ABB") (part "RES0"))
    )
    (comp (ref "R96")
      (value "22.1K")
      (footprint "SMD-0603")
      (description "贴片电阻 1%")
      (libsource (lib "ABB") (part "RES0"))
    )
    (comp (ref "R97")
      (value "300K")
      (footprint "SMD-0603")
      (description "贴片电阻 1%")
      (libsource (lib "ABB") (part "RES0"))
    )
    (comp (ref "R98")
      (value "22.1K")
      (footprint "SMD-0603")
      (description "贴片电阻 1%")
      (libsource (lib "ABB") (part "RES0"))
    )
    (comp (ref "R99")
      (value "300K")
      (footprint "SMD-0603")
      (description "贴片电阻 1%")
      (libsource (lib "ABB") (part "RES0"))
    )
    (comp (ref "R100")
      (value "22.1K")
      (footprint "SMD-0603")
      (description "贴片电阻 1%")
      (libsource (lib "ABB") (part "RES0"))
    )
    (comp (ref "R101")
      (value "0/NC")
      (footprint "SMD-1206")
      (description "贴片电阻 5%")
      (libsource (lib "XiaoyI") (part "RES2"))
    )
    (comp (ref "R102")
      (value "NC")
      (footprint "SMD-0603")
      (description "贴片电阻 5%")
      (libsource (lib "XiaoyI") (part "RES2"))
    )
    (comp (ref "R103")
      (value "NC")
      (footprint "SMD-0603")
      (description "贴片电阻 5%")
      (libsource (lib "") (part "RES2_1"))
    )
    (comp (ref "R104")
      (value "NC")
      (footprint "VR-05")
      (description "可调电阻")
      (libsource (lib "ABB") (part "RES4"))
    )
    (comp (ref "R105")
      (value "1M")
      (footprint "SMD-0603")
      (description "贴片电阻 5%")
      (libsource (lib "") (part "RES2_1"))
    )
    (comp (ref "R106")
      (value "300K")
      (footprint "SMD-0603")
      (description "贴片电阻 1%")
      (libsource (lib "ABB") (part "RES0"))
    )
    (comp (ref "R107")
      (value "22.1K")
      (footprint "SMD-0603")
      (description "贴片电阻 1%")
      (libsource (lib "ABB") (part "RES0"))
    )
    (comp (ref "R108")
      (value "300K")
      (footprint "SMD-0603")
      (description "贴片电阻 1%")
      (libsource (lib "ABB") (part "RES0"))
    )
    (comp (ref "R109")
      (value "22.1K")
      (footprint "SMD-0603")
      (description "贴片电阻 1%")
      (libsource (lib "ABB") (part "RES0"))
    )
    (comp (ref "R110")
      (value "100K")
      (footprint "SMD-0603")
      (description "贴片电阻 5%")
      (libsource (lib "XiaoyI") (part "RES2"))
    )
    (comp (ref "R111")
      (value "300K")
      (footprint "SMD-0603")
      (description "贴片电阻 1%")
      (libsource (lib "ABB") (part "RES0"))
    )
    (comp (ref "R112")
      (value "22.1K")
      (footprint "SMD-0603")
      (description "贴片电阻 1%")
      (libsource (lib "ABB") (part "RES0"))
    )
    (comp (ref "R113")
      (value "300K")
      (footprint "SMD-0603")
      (description "贴片电阻 1%")
      (libsource (lib "ABB") (part "RES0"))
    )
    (comp (ref "R114")
      (value "22.1K")
      (footprint "SMD-0603")
      (description "贴片电阻 1%")
      (libsource (lib "ABB") (part "RES0"))
    )
    (comp (ref "R115")
      (value "300K")
      (footprint "SMD-0603")
      (description "贴片电阻 1%")
      (libsource (lib "ABB") (part "RES0"))
    )
    (comp (ref "R116")
      (value "22.1K")
      (footprint "SMD-0603")
      (description "贴片电阻 1%")
      (libsource (lib "ABB") (part "RES0"))
    )
    (comp (ref "R117")
      (value "NC")
      (footprint "SMD-0603")
      (description "贴片电阻 5%")
      (libsource (lib "") (part "RES2_1"))
    )
    (comp (ref "R118")
      (value "300K")
      (footprint "SMD-0603")
      (description "贴片电阻 1%")
      (libsource (lib "ABB") (part "RES0"))
    )
    (comp (ref "R119")
      (value "22.1K")
      (footprint "SMD-0603")
      (description "贴片电阻 1%")
      (libsource (lib "ABB") (part "RES0"))
    )
    (comp (ref "R120")
      (value "300K")
      (footprint "SMD-0603")
      (description "贴片电阻 1%")
      (libsource (lib "ABB") (part "RES0"))
    )
    (comp (ref "R121")
      (value "22.1K")
      (footprint "SMD-0603")
      (description "贴片电阻 1%")
      (libsource (lib "ABB") (part "RES0"))
    )
    (comp (ref "R122")
      (value "NC")
      (footprint "SMD-0603")
      (description "贴片电阻 5%")
      (libsource (lib "") (part "RES2_1"))
    )
    (comp (ref "R123")
      (value "300K")
      (footprint "SMD-0603")
      (description "贴片电阻 1%")
      (libsource (lib "ABB") (part "RES0"))
    )
    (comp (ref "R124")
      (value "22.1K")
      (footprint "SMD-0603")
      (description "贴片电阻 1%")
      (libsource (lib "ABB") (part "RES0"))
    )
    (comp (ref "R125")
      (value "300K")
      (footprint "SMD-0603")
      (description "贴片电阻 1%")
      (libsource (lib "ABB") (part "RES0"))
    )
    (comp (ref "R126")
      (value "22.1K")
      (footprint "SMD-0603")
      (description "贴片电阻 1%")
      (libsource (lib "ABB") (part "RES0"))
    )
    (comp (ref "R127")
      (value "10K")
      (footprint "SMD-0603")
      (description "贴片电阻 5%")
      (libsource (lib "XiaoyI") (part "RES2"))
    )
    (comp (ref "R128")
      (value "300K")
      (footprint "SMD-0603")
      (description "贴片电阻 1%")
      (libsource (lib "ABB") (part "RES0"))
    )
    (comp (ref "R129")
      (value "22.1K")
      (footprint "SMD-0603")
      (description "贴片电阻 1%")
      (libsource (lib "ABB") (part "RES0"))
    )
    (comp (ref "R130")
      (value "300K")
      (footprint "SMD-0603")
      (description "贴片电阻 1%")
      (libsource (lib "ABB") (part "RES0"))
    )
    (comp (ref "R131")
      (value "22.1K")
      (footprint "SMD-0603")
      (description "贴片电阻 1%")
      (libsource (lib "ABB") (part "RES0"))
    )
    (comp (ref "R132")
      (value "300K")
      (footprint "SMD-0603")
      (description "贴片电阻 1%")
      (libsource (lib "ABB") (part "RES0"))
    )
    (comp (ref "R133")
      (value "22.1K")
      (footprint "SMD-0603")
      (description "贴片电阻 1%")
      (libsource (lib "ABB") (part "RES0"))
    )
    (comp (ref "R134")
      (value "300K")
      (footprint "SMD-0603")
      (description "贴片电阻 1%")
      (libsource (lib "ABB") (part "RES0"))
    )
    (comp (ref "R135")
      (value "22.1K")
      (footprint "SMD-0603")
      (description "贴片电阻 1%")
      (libsource (lib "ABB") (part "RES0"))
    )
    (comp (ref "R136")
      (value "NC")
      (footprint "SMD-0603")
      (description "贴片电阻 5%")
      (libsource (lib "") (part "RES2_2"))
    )
    (comp (ref "R137")
      (value "300K")
      (footprint "SMD-0603")
      (description "贴片电阻 1%")
      (libsource (lib "ABB") (part "RES0"))
    )
    (comp (ref "R138")
      (value "22.1K")
      (footprint "SMD-0603")
      (description "贴片电阻 1%")
      (libsource (lib "ABB") (part "RES0"))
    )
    (comp (ref "R139")
      (value "300K")
      (footprint "SMD-0603")
      (description "贴片电阻 1%")
      (libsource (lib "ABB") (part "RES0"))
    )
    (comp (ref "R140")
      (value "22.1K")
      (footprint "SMD-0603")
      (description "贴片电阻 1%")
      (libsource (lib "ABB") (part "RES0"))
    )
    (comp (ref "R141")
      (value "300K")
      (footprint "SMD-0603")
      (description "贴片电阻 1%")
      (libsource (lib "ABB") (part "RES0"))
    )
    (comp (ref "R142")
      (value "22.1K")
      (footprint "SMD-0603")
      (description "贴片电阻 1%")
      (libsource (lib "ABB") (part "RES0"))
    )
    (comp (ref "R143")
      (value "300K")
      (footprint "SMD-0603")
      (description "贴片电阻 1%")
      (libsource (lib "ABB") (part "RES0"))
    )
    (comp (ref "R144")
      (value "22.1K")
      (footprint "SMD-0603")
      (description "贴片电阻 1%")
      (libsource (lib "ABB") (part "RES0"))
    )
    (comp (ref "R145")
      (value "0/NC")
      (footprint "SMD-1206")
      (description "贴片电阻 5%")
      (libsource (lib "XiaoyI") (part "RES2"))
    )
    (comp (ref "TVS1")
      (value "PSD05C-LF-T7")
      (footprint "SOD-323")
      (description "单向TVS")
      (libsource (lib "XiaoyI") (part "TVS-S"))
    )
    (comp (ref "TVS2")
      (value "PSD05C-LF-T7")
      (footprint "SOD-323")
      (description "单向TVS")
      (libsource (lib "XiaoyI") (part "TVS-S"))
    )
    (comp (ref "TVS5")
      (value "PSD05C-LF-T7")
      (footprint "SOD-323")
      (description "单向TVS")
      (libsource (lib "XiaoyI") (part "TVS-S"))
    )
    (comp (ref "TVS6")
      (value "PSD05C-LF-T7")
      (footprint "SOD-323")
      (description "单向TVS")
      (libsource (lib "XiaoyI") (part "TVS-S"))
    )
    (comp (ref "TVS7")
      (value "PSD05C-LF-T7")
      (footprint "SOD-323")
      (description "单向TVS")
      (libsource (lib "XiaoyI") (part "TVS-S"))
    )
    (comp (ref "TVS8")
      (value "PSD05C-LF-T7")
      (footprint "SOD-323")
      (description "单向TVS")
      (libsource (lib "XiaoyI") (part "TVS-S"))
    )
    (comp (ref "TVS9")
      (value "PSD05C-LF-T7")
      (footprint "SOD-323")
      (description "单向TVS")
      (libsource (lib "XiaoyI") (part "TVS-S"))
    )
    (comp (ref "TVS10")
      (value "PSD05C-LF-T7")
      (footprint "SOD-323")
      (description "单向TVS")
      (libsource (lib "XiaoyI") (part "TVS-S"))
    )
    (comp (ref "TVS11")
      (value "PSD05C-LF-T7")
      (footprint "SOD-323")
      (description "单向TVS")
      (libsource (lib "XiaoyI") (part "TVS-S"))
    )
    (comp (ref "TVS12")
      (value "PSD05C-LF-T7")
      (footprint "SOD-323")
      (description "单向TVS")
      (libsource (lib "XiaoyI") (part "TVS-S"))
    )
    (comp (ref "TVS13")
      (value "PSD05C-LF-T7")
      (footprint "SOD-323")
      (description "单向TVS")
      (libsource (lib "XiaoyI") (part "TVS-S"))
    )
    (comp (ref "TVS14")
      (value "PSD05C-LF-T7")
      (footprint "SOD-323")
      (description "单向TVS")
      (libsource (lib "XiaoyI") (part "TVS-S"))
    )
    (comp (ref "TVS15")
      (value "PSD05C-LF-T7")
      (footprint "SOD-323")
      (description "单向TVS")
      (libsource (lib "XiaoyI") (part "TVS-S"))
    )
    (comp (ref "TVS16")
      (value "PSD05C-LF-T7")
      (footprint "SOD-323")
      (description "单向TVS")
      (libsource (lib "XiaoyI") (part "TVS-S"))
    )
    (comp (ref "TVS17")
      (value "PSD05C-LF-T7")
      (footprint "SOD-323")
      (description "单向TVS")
      (libsource (lib "XiaoyI") (part "TVS-S"))
    )
    (comp (ref "TVS18")
      (value "PSD05C-LF-T7")
      (footprint "SOD-323")
      (description "单向TVS")
      (libsource (lib "XiaoyI") (part "TVS-S"))
    )
    (comp (ref "TVS19")
      (value "PSD05C-LF-T7")
      (footprint "SOD-323")
      (description "单向TVS")
      (libsource (lib "XiaoyI") (part "TVS-S"))
    )
    (comp (ref "TVS20")
      (value "PSD05C-LF-T7")
      (footprint "SOD-323")
      (description "单向TVS")
      (libsource (lib "XiaoyI") (part "TVS-S"))
    )
    (comp (ref "TVS21")
      (value "PSD05C-LF-T7")
      (footprint "SOD-323")
      (description "单向TVS")
      (libsource (lib "XiaoyI") (part "TVS-S"))
    )
    (comp (ref "TVS22")
      (value "PSD05C-LF-T7")
      (footprint "SOD-323")
      (description "单向TVS")
      (libsource (lib "XiaoyI") (part "TVS-S"))
    )
    (comp (ref "TVS23")
      (value "PSD05C-LF-T7")
      (footprint "SOD-323")
      (description "单向TVS")
      (libsource (lib "XiaoyI") (part "TVS-S"))
    )
    (comp (ref "TVS24")
      (value "PSD05C-LF-T7")
      (footprint "SOD-323")
      (description "单向TVS")
      (libsource (lib "XiaoyI") (part "TVS-S"))
    )
    (comp (ref "TVS25")
      (value "PSD05C-LF-T7")
      (footprint "SOD-323")
      (description "单向TVS")
      (libsource (lib "XiaoyI") (part "TVS-S"))
    )
    (comp (ref "TVS26")
      (value "PSD05C-LF-T7")
      (footprint "SOD-323")
      (description "单向TVS")
      (libsource (lib "XiaoyI") (part "TVS-S"))
    )
    (comp (ref "TVS27")
      (value "PSD05C-LF-T7")
      (footprint "SOD-323")
      (description "单向TVS")
      (libsource (lib "XiaoyI") (part "TVS-S"))
    )
    (comp (ref "TVS28")
      (value "PSD05C-LF-T7")
      (footprint "SOD-323")
      (description "单向TVS")
      (libsource (lib "XiaoyI") (part "TVS-S"))
    )
    (comp (ref "TVS29")
      (value "PSD05C-LF-T7")
      (footprint "SOD-323")
      (description "单向TVS")
      (libsource (lib "XiaoyI") (part "TVS-S"))
    )
    (comp (ref "TVS30")
      (value "PSD05C-LF-T7")
      (footprint "SOD-323")
      (description "单向TVS")
      (libsource (lib "XiaoyI") (part "TVS-S"))
    )
    (comp (ref "TVS31")
      (value "PSD05C-LF-T7")
      (footprint "SOD-323")
      (description "单向TVS")
      (libsource (lib "XiaoyI") (part "TVS-S"))
    )
    (comp (ref "TVS32")
      (value "PSD05C-LF-T7")
      (footprint "SOD-323")
      (description "单向TVS")
      (libsource (lib "XiaoyI") (part "TVS-S"))
    )
    (comp (ref "TVS33")
      (value "PSD05C-LF-T7")
      (footprint "SOD-323")
      (description "单向TVS")
      (libsource (lib "XiaoyI") (part "TVS-S"))
    )
    (comp (ref "TVS34")
      (value "PSD05C-LF-T7")
      (footprint "SOD-323")
      (description "单向TVS")
      (libsource (lib "XiaoyI") (part "TVS-S"))
    )
    (comp (ref "TVS35")
      (value "PSD05C-LF-T7")
      (footprint "SOD-323")
      (description "单向TVS")
      (libsource (lib "XiaoyI") (part "TVS-S"))
    )
    (comp (ref "TVS36")
      (value "PSD05C-LF-T7")
      (footprint "SOD-323")
      (description "单向TVS")
      (libsource (lib "XiaoyI") (part "TVS-S"))
    )
    (comp (ref "U8")
      (value "OPA2376AID/NC")
      (footprint "SOIC-8")
      (description "运放")
      (libsource (lib "XiaoyI") (part "LM358"))
    )
    (comp (ref "U9")
      (value "ADS1299IPAG")
      (footprint "LQFP-64")
      (libsource (lib "stm32") (part "ADS1299IPAG"))
    )
    (comp (ref "U11")
      (value "OPA2376AID/NC")
      (footprint "SOIC-8")
      (description "运放")
      (libsource (lib "XiaoyI") (part "LM358"))
    )
    (comp (ref "U12")
      (value "OPA2376AID/NC")
      (footprint "SOIC-8")
      (description "运放")
      (libsource (lib "XiaoyI") (part "LM358"))
    )
    (comp (ref "U13")
      (value "ADS1299IPAG")
      (footprint "LQFP-64")
      (libsource (lib "stm32") (part "ADS1299IPAG"))
    )
    (comp (ref "U14")
      (value "OPA2376AID/NC")
      (footprint "SOIC-8")
      (description "运放")
      (libsource (lib "XiaoyI") (part "LM358"))
    )
  )
  (nets
    (net (code "1") (name "/ADS129x_CS") (class "Default")
      (node (ref "U9") (pin "39") (pinfunction "~{CS}_39") (pintype "passive"))
    )
    (net (code "2") (name "/ADS129x_CS2") (class "Default")
      (node (ref "U13") (pin "39") (pinfunction "~{CS}_39") (pintype "passive"))
    )
    (net (code "3") (name "/ADS129x_DIN") (class "Default")
      (node (ref "U13") (pin "34") (pinfunction "DIN_34") (pintype "passive"))
      (node (ref "U9") (pin "34") (pinfunction "DIN_34") (pintype "passive"))
    )
    (net (code "4") (name "/ADS129x_DOUT") (class "Default")
      (node (ref "U13") (pin "43") (pinfunction "DOUT_43") (pintype "passive"))
      (node (ref "U9") (pin "43") (pinfunction "DOUT_43") (pintype "passive"))
    )
    (net (code "5") (name "/ADS129x_DRDY") (class "Default")
      (node (ref "U9") (pin "47") (pinfunction "~{DRDY}_47") (pintype "passive"))
    )
    (net (code "6") (name "/ADS129x_DRDY2") (class "Default")
      (node (ref "U13") (pin "47") (pinfunction "~{DRDY}_47") (pintype "passive"))
    )
    (net (code "7") (name "/ADS129x_SCLK") (class "Default")
      (node (ref "U13") (pin "40") (pinfunction "SCLK_40") (pintype "passive"))
      (node (ref "U9") (pin "40") (pinfunction "SCLK_40") (pintype "passive"))
    )
    (net (code "8") (name "/BIAS_ELEC") (class "Default")
      (node (ref "P12") (pin "1") (pinfunction "1_1") (pintype "passive"))
      (node (ref "P13") (pin "1") (pinfunction "1_1") (pintype "passive"))
    )
    (net (code "9") (name "/BIAS_ELEC2") (class "Default")
      (node (ref "P18") (pin "1") (pinfunction "1_1") (pintype "passive"))
      (node (ref "P19") (pin "1") (pinfunction "1_1") (pintype "passive"))
    )
    (net (code "10") (name "/BIAS_SHD") (class "Default")
      (node (ref "U8") (pin "1") (pinfunction "OUT1_1") (pintype "output"))
      (node (ref "U8") (pin "2") (pinfunction "IN1-_2") (pintype "input"))
    )
    (net (code "11") (name "/BIAS_SHD2") (class "Default")
      (node (ref "U12") (pin "1") (pinfunction "OUT1_1") (pintype "output"))
      (node (ref "U12") (pin "2") (pinfunction "IN1-_2") (pintype "input"))
    )
    (net (code "12") (name "/CIN2P") (class "Default")
      (node (ref "P29") (pin "17") (pinfunction "17_17") (pintype "passive"))
      (node (ref "R111") (pin "1") (pinfunction "1_1") (pintype "passive"))
    )
    (net (code "13") (name "/CINN1") (class "Default")
      (node (ref "P16") (pin "2") (pinfunction "2_2") (pintype "passive"))
      (node (ref "R62") (pin "1") (pinfunction "1_1") (pintype "passive"))
    )
    (net (code "14") (name "/CINN2") (class "Default")
      (node (ref "P16") (pin "4") (pinfunction "4_4") (pintype "passive"))
      (node (ref "R69") (pin "1") (pinfunction "1_1") (pintype "passive"))
    )
    (net (code "15") (name "/CINN3") (class "Default")
      (node (ref "P16") (pin "6") (pinfunction "6_6") (pintype "passive"))
      (node (ref "R74") (pin "1") (pinfunction "1_1") (pintype "passive"))
    )
    (net (code "16") (name "/CINN4") (class "Default")
      (node (ref "P16") (pin "8") (pinfunction "8_8") (pintype "passive"))
      (node (ref "R81") (pin "1") (pinfunction "1_1") (pintype "passive"))
    )
    (net (code "17") (name "/CINN5") (class "Default")
      (node (ref "P16") (pin "10") (pinfunction "10_10") (pintype "passive"))
      (node (ref "R86") (pin "1") (pinfunction "1_1") (pintype "passive"))
    )
    (net (code "18") (name "/CINN6") (class "Default")
      (node (ref "P16") (pin "12") (pinfunction "12_12") (pintype "passive"))
      (node (ref "R90") (pin "1") (pinfunction "1_1") (pintype "passive"))
    )
    (net (code "19") (name "/CINN7") (class "Default")
      (node (ref "P16") (pin "14") (pinfunction "14_14") (pintype "passive"))
      (node (ref "R95") (pin "1") (pinfunction "1_1") (pintype "passive"))
    )
    (net (code "20") (name "/CINN8") (class "Default")
      (node (ref "P16") (pin "16") (pinfunction "16_16") (pintype "passive"))
      (node (ref "R99") (pin "1") (pinfunction "1_1") (pintype "passive"))
    )
    (net (code "21") (name "/CINN21") (class "Default")
      (node (ref "P29") (pin "2") (pinfunction "2_2") (pintype "passive"))
      (node (ref "R108") (pin "1") (pinfunction "1_1") (pintype "passive"))
    )
    (net (code "22") (name "/CINN22") (class "Default")
      (node (ref "P29") (pin "4") (pinfunction "4_4") (pintype "passive"))
      (node (ref "R115") (pin "1") (pinfunction "1_1") (pintype "passive"))
    )
    (net (code "23") (name "/CINN23") (class "Default")
      (node (ref "P29") (pin "6") (pinfunction "6_6") (pintype "passive"))
      (node (ref "R120") (pin "1") (pinfunction "1_1") (pintype "passive"))
    )
    (net (code "24") (name "/CINN24") (class "Default")
      (node (ref "P29") (pin "8") (pinfunction "8_8") (pintype "passive"))
      (node (ref "R125") (pin "1") (pinfunction "1_1") (pintype "passive"))
    )
    (net (code "25") (name "/CINN25") (class "Default")
      (node (ref "P29") (pin "10") (pinfunction "10_10") (pintype "passive"))
      (node (ref "R130") (pin "1") (pinfunction "1_1") (pintype "passive"))
    )
    (net (code "26") (name "/CINN26") (class "Default")
      (node (ref "P29") (pin "12") (pinfunction "12_12") (pintype "passive"))
      (node (ref "R134") (pin "1") (pinfunction "1_1") (pintype "passive"))
    )
    (net (code "27") (name "/CINN27") (class "Default")
      (node (ref "P29") (pin "14") (pinfunction "14_14") (pintype "passive"))
      (node (ref "R139") (pin "1") (pinfunction "1_1") (pintype "passive"))
    )
    (net (code "28") (name "/CINN28") (class "Default")
      (node (ref "P29") (pin "16") (pinfunction "16_16") (pintype "passive"))
      (node (ref "R143") (pin "1") (pinfunction "1_1") (pintype "passive"))
    )
    (net (code "29") (name "/CINP") (class "Default")
      (node (ref "P16") (pin "17") (pinfunction "17_17") (pintype "passive"))
      (node (ref "R65") (pin "1") (pinfunction "1_1") (pintype "passive"))
    )
    (net (code "30") (name "/CINP1") (class "Default")
      (node (ref "P16") (pin "1") (pinfunction "1_1") (pintype "passive"))
      (node (ref "R60") (pin "1") (pinfunction "1_1") (pintype "passive"))
    )
    (net (code "31") (name "/CINP2") (class "Default")
      (node (ref "P16") (pin "3") (pinfunction "3_3") (pintype "passive"))
      (node (ref "R67") (pin "1") (pinfunction "1_1") (pintype "passive"))
    )
    (net (code "32") (name "/CINP3") (class "Default")
      (node (ref "P16") (pin "5") (pinfunction "5_5") (pintype "passive"))
      (node (ref "R72") (pin "1") (pinfunction "1_1") (pintype "passive"))
    )
    (net (code "33") (name "/CINP4") (class "Default")
      (node (ref "P16") (pin "7") (pinfunction "7_7") (pintype "passive"))
      (node (ref "R77") (pin "1") (pinfunction "1_1") (pintype "passive"))
    )
    (net (code "34") (name "/CINP5") (class "Default")
      (node (ref "P16") (pin "9") (pinfunction "9_9") (pintype "passive"))
      (node (ref "R84") (pin "1") (pinfunction "1_1") (pintype "passive"))
    )
    (net (code "35") (name "/CINP6") (class "Default")
      (node (ref "P16") (pin "11") (pinfunction "11_11") (pintype "passive"))
      (node (ref "R88") (pin "1") (pinfunction "1_1") (pintype "passive"))
    )
    (net (code "36") (name "/CINP7") (class "Default")
      (node (ref "P16") (pin "13") (pinfunction "13_13") (pintype "passive"))
      (node (ref "R93") (pin "1") (pinfunction "1_1") (pintype "passive"))
    )
    (net (code "37") (name "/CINP8") (class "Default")
      (node (ref "P16") (pin "15") (pinfunction "15_15") (pintype "passive"))
      (node (ref "R97") (pin "1") (pinfunction "1_1") (pintype "passive"))
    )
    (net (code "38") (name "/CINP21") (class "Default")
      (node (ref "P29") (pin "1") (pinfunction "1_1") (pintype "passive"))
      (node (ref "R106") (pin "1") (pinfunction "1_1") (pintype "passive"))
    )
    (net (code "39") (name "/CINP22") (class "Default")
      (node (ref "P29") (pin "3") (pinfunction "3_3") (pintype "passive"))
      (node (ref "R113") (pin "1") (pinfunction "1_1") (pintype "passive"))
    )
    (net (code "40") (name "/CINP23") (class "Default")
      (node (ref "P29") (pin "5") (pinfunction "5_5") (pintype "passive"))
      (node (ref "R118") (pin "1") (pinfunction "1_1") (pintype "passive"))
    )
    (net (code "41") (name "/CINP24") (class "Default")
      (node (ref "P29") (pin "7") (pinfunction "7_7") (pintype "passive"))
      (node (ref "R123") (pin "1") (pinfunction "1_1") (pintype "passive"))
    )
    (net (code "42") (name "/CINP25") (class "Default")
      (node (ref "P29") (pin "9") (pinfunction "9_9") (pintype "passive"))
      (node (ref "R128") (pin "1") (pinfunction "1_1") (pintype "passive"))
    )
    (net (code "43") (name "/CINP26") (class "Default")
      (node (ref "P29") (pin "11") (pinfunction "11_11") (pintype "passive"))
      (node (ref "R132") (pin "1") (pinfunction "1_1") (pintype "passive"))
    )
    (net (code "44") (name "/CINP27") (class "Default")
      (node (ref "P29") (pin "13") (pinfunction "13_13") (pintype "passive"))
      (node (ref "R137") (pin "1") (pinfunction "1_1") (pintype "passive"))
    )
    (net (code "45") (name "/CINP28") (class "Default")
      (node (ref "P29") (pin "15") (pinfunction "15_15") (pintype "passive"))
      (node (ref "R141") (pin "1") (pinfunction "1_1") (pintype "passive"))
    )
    (net (code "46") (name "/IN1N") (class "Default")
      (node (ref "C46") (pin "2") (pinfunction "2_2") (pintype "passive"))
      (node (ref "R63") (pin "2") (pinfunction "2_2") (pintype "passive"))
      (node (ref "TVS2") (pin "2") (pinfunction "B_2") (pintype "passive"))
      (node (ref "U9") (pin "15") (pinfunction "IN1N_15") (pintype "passive"))
    )
    (net (code "47") (name "/IN1P") (class "Default")
      (node (ref "C43") (pin "2") (pinfunction "2_2") (pintype "passive"))
      (node (ref "R61") (pin "2") (pinfunction "2_2") (pintype "passive"))
      (node (ref "TVS1") (pin "2") (pinfunction "B_2") (pintype "passive"))
      (node (ref "U9") (pin "16") (pinfunction "IN1P_16") (pintype "passive"))
    )
    (net (code "48") (name "/IN2N") (class "Default")
      (node (ref "C58") (pin "2") (pinfunction "2_2") (pintype "passive"))
      (node (ref "R70") (pin "2") (pinfunction "2_2") (pintype "passive"))
      (node (ref "TVS7") (pin "2") (pinfunction "B_2") (pintype "passive"))
      (node (ref "U9") (pin "13") (pinfunction "IN2N_13") (pintype "passive"))
    )
    (net (code "49") (name "/IN2P") (class "Default")
      (node (ref "C53") (pin "2") (pinfunction "2_2") (pintype "passive"))
      (node (ref "R68") (pin "2") (pinfunction "2_2") (pintype "passive"))
      (node (ref "TVS6") (pin "2") (pinfunction "B_2") (pintype "passive"))
      (node (ref "U9") (pin "14") (pinfunction "IN2P_14") (pintype "passive"))
    )
    (net (code "50") (name "/IN3N") (class "Default")
      (node (ref "C62") (pin "2") (pinfunction "2_2") (pintype "passive"))
      (node (ref "R75") (pin "2") (pinfunction "2_2") (pintype "passive"))
      (node (ref "TVS9") (pin "2") (pinfunction "B_2") (pintype "passive"))
      (node (ref "U9") (pin "11") (pinfunction "IN3N_11") (pintype "passive"))
    )
    (net (code "51") (name "/IN3P") (class "Default")
      (node (ref "C60") (pin "2") (pinfunction "2_2") (pintype "passive"))
      (node (ref "R73") (pin "2") (pinfunction "2_2") (pintype "passive"))
      (node (ref "TVS8") (pin "2") (pinfunction "B_2") (pintype "passive"))
      (node (ref "U9") (pin "12") (pinfunction "IN3P_12") (pintype "passive"))
    )
    (net (code "52") (name "/IN4N") (class "Default")
      (node (ref "C66") (pin "2") (pinfunction "2_2") (pintype "passive"))
      (node (ref "R82") (pin "2") (pinfunction "2_2") (pintype "passive"))
      (node (ref "TVS11") (pin "2") (pinfunction "B_2") (pintype "passive"))
      (node (ref "U9") (pin "9") (pinfunction "IN4N_9") (pintype "passive"))
    )
    (net (code "53") (name "/IN4P") (class "Default")
      (node (ref "C64") (pin "2") (pinfunction "2_2") (pintype "passive"))
      (node (ref "R80") (pin "2") (pinfunction "2_2") (pintype "passive"))
      (node (ref "TVS10") (pin "2") (pinfunction "B_2") (pintype "passive"))
      (node (ref "U9") (pin "10") (pinfunction "IN4P_10") (pintype "passive"))
    )
    (net (code "54") (name "/IN5N") (class "Default")
      (node (ref "C70") (pin "2") (pinfunction "2_2") (pintype "passive"))
      (node (ref "R87") (pin "2") (pinfunction "2_2") (pintype "passive"))
      (node (ref "TVS13") (pin "2") (pinfunction "B_2") (pintype "passive"))
      (node (ref "U9") (pin "7") (pinfunction "IN5N_7") (pintype "passive"))
    )
    (net (code "55") (name "/IN5P") (class "Default")
      (node (ref "C68") (pin "2") (pinfunction "2_2") (pintype "passive"))
      (node (ref "R85") (pin "2") (pinfunction "2_2") (pintype "passive"))
      (node (ref "TVS12") (pin "2") (pinfunction "B_2") (pintype "passive"))
      (node (ref "U9") (pin "8") (pinfunction "IN5P_8") (pintype "passive"))
    )
    (net (code "56") (name "/IN6N") (class "Default")
      (node (ref "C75") (pin "2") (pinfunction "2_2") (pintype "passive"))
      (node (ref "R91") (pin "2") (pinfunction "2_2") (pintype "passive"))
      (node (ref "TVS15") (pin "2") (pinfunction "B_2") (pintype "passive"))
      (node (ref "U9") (pin "5") (pinfunction "IN6N_5") (pintype "passive"))
    )
    (net (code "57") (name "/IN6P") (class "Default")
      (node (ref "C73") (pin "2") (pinfunction "2_2") (pintype "passive"))
      (node (ref "R89") (pin "2") (pinfunction "2_2") (pintype "passive"))
      (node (ref "TVS14") (pin "2") (pinfunction "B_2") (pintype "passive"))
      (node (ref "U9") (pin "6") (pinfunction "IN6P_6") (pintype "passive"))
    )
    (net (code "58") (name "/IN7N") (class "Default")
      (node (ref "C85") (pin "2") (pinfunction "2_2") (pintype "passive"))
      (node (ref "R96") (pin "2") (pinfunction "2_2") (pintype "passive"))
      (node (ref "TVS17") (pin "2") (pinfunction "B_2") (pintype "passive"))
      (node (ref "U9") (pin "3") (pinfunction "IN7N_3") (pintype "passive"))
    )
    (net (code "59") (name "/IN7P") (class "Default")
      (node (ref "C83") (pin "2") (pinfunction "2_2") (pintype "passive"))
      (node (ref "R94") (pin "2") (pinfunction "2_2") (pintype "passive"))
      (node (ref "TVS16") (pin "2") (pinfunction "B_2") (pintype "passive"))
      (node (ref "U9") (pin "4") (pinfunction "IN7P_4") (pintype "passive"))
    )
    (net (code "60") (name "/IN8N") (class "Default")
      (node (ref "C89") (pin "2") (pinfunction "2_2") (pintype "passive"))
      (node (ref "R100") (pin "2") (pinfunction "2_2") (pintype "passive"))
      (node (ref "TVS19") (pin "2") (pinfunction "B_2") (pintype "passive"))
      (node (ref "U9") (pin "1") (pinfunction "IN8N_1") (pintype "passive"))
    )
    (net (code "61") (name "/IN8P") (class "Default")
      (node (ref "C87") (pin "2") (pinfunction "2_2") (pintype "passive"))
      (node (ref "R98") (pin "2") (pinfunction "2_2") (pintype "passive"))
      (node (ref "TVS18") (pin "2") (pinfunction "B_2") (pintype "passive"))
      (node (ref "U9") (pin "2") (pinfunction "IN8P_2") (pintype "passive"))
    )
    (net (code "62") (name "/IN21N") (class "Default")
      (node (ref "C105") (pin "2") (pinfunction "2_2") (pintype "passive"))
      (node (ref "R109") (pin "2") (pinfunction "2_2") (pintype "passive"))
      (node (ref "TVS21") (pin "2") (pinfunction "B_2") (pintype "passive"))
      (node (ref "U13") (pin "15") (pinfunction "IN1N_15") (pintype "passive"))
    )
    (net (code "63") (name "/IN21P") (class "Default")
      (node (ref "C103") (pin "2") (pinfunction "2_2") (pintype "passive"))
      (node (ref "R107") (pin "2") (pinfunction "2_2") (pintype "passive"))
      (node (ref "TVS20") (pin "2") (pinfunction "B_2") (pintype "passive"))
      (node (ref "U13") (pin "16") (pinfunction "IN1P_16") (pintype "passive"))
    )
    (net (code "64") (name "/IN22N") (class "Default")
      (node (ref "C111") (pin "2") (pinfunction "2_2") (pintype "passive"))
      (node (ref "R116") (pin "2") (pinfunction "2_2") (pintype "passive"))
      (node (ref "TVS24") (pin "2") (pinfunction "B_2") (pintype "passive"))
      (node (ref "U13") (pin "13") (pinfunction "IN2N_13") (pintype "passive"))
    )
    (net (code "65") (name "/IN22P") (class "Default")
      (node (ref "C109") (pin "2") (pinfunction "2_2") (pintype "passive"))
      (node (ref "R114") (pin "2") (pinfunction "2_2") (pintype "passive"))
      (node (ref "TVS23") (pin "2") (pinfunction "B_2") (pintype "passive"))
      (node (ref "U13") (pin "14") (pinfunction "IN2P_14") (pintype "passive"))
    )
    (net (code "66") (name "/IN23N") (class "Default")
      (node (ref "C115") (pin "2") (pinfunction "2_2") (pintype "passive"))
      (node (ref "R121") (pin "2") (pinfunction "2_2") (pintype "passive"))
      (node (ref "TVS26") (pin "2") (pinfunction "B_2") (pintype "passive"))
      (node (ref "U13") (pin "11") (pinfunction "IN3N_11") (pintype "passive"))
    )
    (net (code "67") (name "/IN23P") (class "Default")
      (node (ref "C113") (pin "2") (pinfunction "2_2") (pintype "passive"))
      (node (ref "R119") (pin "2") (pinfunction "2_2") (pintype "passive"))
      (node (ref "TVS25") (pin "2") (pinfunction "B_2") (pintype "passive"))
      (node (ref "U13") (pin "12") (pinfunction "IN3P_12") (pintype "passive"))
    )
    (net (code "68") (name "/IN24N") (class "Default")
      (node (ref "C119") (pin "2") (pinfunction "2_2") (pintype "passive"))
      (node (ref "R126") (pin "2") (pinfunction "2_2") (pintype "passive"))
      (node (ref "TVS28") (pin "2") (pinfunction "B_2") (pintype "passive"))
      (node (ref "U13") (pin "9") (pinfunction "IN4N_9") (pintype "passive"))
    )
    (net (code "69") (name "/IN24P") (class "Default")
      (node (ref "C117") (pin "2") (pinfunction "2_2") (pintype "passive"))
      (node (ref "R124") (pin "2") (pinfunction "2_2") (pintype "passive"))
      (node (ref "TVS27") (pin "2") (pinfunction "B_2") (pintype "passive"))
      (node (ref "U13") (pin "10") (pinfunction "IN4P_10") (pintype "passive"))
    )
    (net (code "70") (name "/IN25N") (class "Default")
      (node (ref "C123") (pin "2") (pinfunction "2_2") (pintype "passive"))
      (node (ref "R131") (pin "2") (pinfunction "2_2") (pintype "passive"))
      (node (ref "TVS30") (pin "2") (pinfunction "B_2") (pintype "passive"))
      (node (ref "U13") (pin "7") (pinfunction "IN5N_7") (pintype "passive"))
    )
    (net (code "71") (name "/IN25P") (class "Default")
      (node (ref "C121") (pin "2") (pinfunction "2_2") (pintype "passive"))
      (node (ref "R129") (pin "2") (pinfunction "2_2") (pintype "passive"))
      (node (ref "TVS29") (pin "2") (pinfunction "B_2") (pintype "passive"))
      (node (ref "U13") (pin "8") (pinfunction "IN5P_8") (pintype "passive"))
    )
    (net (code "72") (name "/IN26N") (class "Default")
      (node (ref "C128") (pin "2") (pinfunction "2_2") (pintype "passive"))
      (node (ref "R135") (pin "2") (pinfunction "2_2") (pintype "passive"))
      (node (ref "TVS32") (pin "2") (pinfunction "B_2") (pintype "passive"))
      (node (ref "U13") (pin "5") (pinfunction "IN6N_5") (pintype "passive"))
    )
    (net (code "73") (name "/IN26P") (class "Default")
      (node (ref "C126") (pin "2") (pinfunction "2_2") (pintype "passive"))
      (node (ref "R133") (pin "2") (pinfunction "2_2") (pintype "passive"))
      (node (ref "TVS31") (pin "2") (pinfunction "B_2") (pintype "passive"))
      (node (ref "U13") (pin "6") (pinfunction "IN6P_6") (pintype "passive"))
    )
    (net (code "74") (name "/IN27N") (class "Default")
      (node (ref "C138") (pin "2") (pinfunction "2_2") (pintype "passive"))
      (node (ref "R140") (pin "2") (pinfunction "2_2") (pintype "passive"))
      (node (ref "TVS34") (pin "2") (pinfunction "B_2") (pintype "passive"))
      (node (ref "U13") (pin "3") (pinfunction "IN7N_3") (pintype "passive"))
    )
    (net (code "75") (name "/IN27P") (class "Default")
      (node (ref "C136") (pin "2") (pinfunction "2_2") (pintype "passive"))
      (node (ref "R138") (pin "2") (pinfunction "2_2") (pintype "passive"))
      (node (ref "TVS33") (pin "2") (pinfunction "B_2") (pintype "passive"))
      (node (ref "U13") (pin "4") (pinfunction "IN7P_4") (pintype "passive"))
    )
    (net (code "76") (name "/IN28N") (class "Default")
      (node (ref "C142") (pin "2") (pinfunction "2_2") (pintype "passive"))
      (node (ref "R144") (pin "2") (pinfunction "2_2") (pintype "passive"))
      (node (ref "TVS36") (pin "2") (pinfunction "B_2") (pintype "passive"))
      (node (ref "U13") (pin "1") (pinfunction "IN8N_1") (pintype "passive"))
    )
    (net (code "77") (name "/IN28P") (class "Default")
      (node (ref "C140") (pin "2") (pinfunction "2_2") (pintype "passive"))
      (node (ref "R142") (pin "2") (pinfunction "2_2") (pintype "passive"))
      (node (ref "TVS35") (pin "2") (pinfunction "B_2") (pintype "passive"))
      (node (ref "U13") (pin "2") (pinfunction "IN8P_2") (pintype "passive"))
    )
    (net (code "78") (name "AVDD") (class "Default")
      (node (ref "C124") (pin "2") (pinfunction "2_2") (pintype "passive"))
      (node (ref "C143") (pin "2") (pinfunction "2_2") (pintype "passive"))
      (node (ref "C144") (pin "2") (pinfunction "2_2") (pintype "passive"))
      (node (ref "C145") (pin "2") (pinfunction "2_2") (pintype "passive"))
      (node (ref "C146") (pin "2") (pinfunction "2_2") (pintype "passive"))
      (node (ref "C147") (pin "2") (pinfunction "2_2") (pintype "passive"))
      (node (ref "C35") (pin "2") (pinfunction "2_2") (pintype "passive"))
      (node (ref "C71") (pin "2") (pinfunction "2_2") (pintype "passive"))
      (node (ref "C90") (pin "2") (pinfunction "2_2") (pintype "passive"))
      (node (ref "C91") (pin "2") (pinfunction "2_2") (pintype "passive"))
      (node (ref "C92") (pin "2") (pinfunction "2_2") (pintype "passive"))
      (node (ref "C93") (pin "2") (pinfunction "2_2") (pintype "passive"))
      (node (ref "C94") (pin "2") (pinfunction "2_2") (pintype "passive"))
      (node (ref "C98") (pin "2") (pinfunction "2_2") (pintype "passive"))
      (node (ref "R103") (pin "1") (pinfunction "1_1") (pintype "passive"))
      (node (ref "R117") (pin "1") (pinfunction "1_1") (pintype "passive"))
      (node (ref "R53") (pin "1") (pinfunction "1_1") (pintype "passive"))
      (node (ref "R71") (pin "1") (pinfunction "1_1") (pintype "passive"))
      (node (ref "U11") (pin "8") (pinfunction "V+_8") (pintype "power_in"))
      (node (ref "U12") (pin "8") (pinfunction "V+_8") (pintype "power_in"))
      (node (ref "U13") (pin "19") (pinfunction "AVDD_19") (pintype "passive"))
      (node (ref "U13") (pin "21") (pinfunction "AVDD_21") (pintype "passive"))
      (node (ref "U13") (pin "22") (pinfunction "AVDD_22") (pintype "passive"))
      (node (ref "U13") (pin "54") (pinfunction "AVDD1_54") (pintype "passive"))
      (node (ref "U13") (pin "56") (pinfunction "AVDD_56") (pintype "passive"))
      (node (ref "U13") (pin "59") (pinfunction "AVDD_59") (pintype "passive"))
      (node (ref "U14") (pin "8") (pinfunction "V+_8") (pintype "power_in"))
      (node (ref "U8") (pin "8") (pinfunction "V+_8") (pintype "power_in"))
      (node (ref "U9") (pin "19") (pinfunction "AVDD_19") (pintype "passive"))
      (node (ref "U9") (pin "21") (pinfunction "AVDD_21") (pintype "passive"))
      (node (ref "U9") (pin "22") (pinfunction "AVDD_22") (pintype "passive"))
      (node (ref "U9") (pin "54") (pinfunction "AVDD1_54") (pintype "passive"))
      (node (ref "U9") (pin "56") (pinfunction "AVDD_56") (pintype "passive"))
      (node (ref "U9") (pin "59") (pinfunction "AVDD_59") (pintype "passive"))
    )
    (net (code "79") (name "AVSS") (class "Default")
      (node (ref "C102") (pin "1") (pinfunction "1_1") (pintype "passive"))
      (node (ref "C103") (pin "1") (pinfunction "1_1") (pintype "passive"))
      (node (ref "C104") (pin "1") (pinfunction "1_1") (pintype "passive"))
      (node (ref "C105") (pin "1") (pinfunction "1_1") (pintype "passive"))
      (node (ref "C106") (pin "1") (pinfunction "1_1") (pintype "passive"))
      (node (ref "C107") (pin "1") (pinfunction "1_1") (pintype "passive"))
      (node (ref "C108") (pin "1") (pinfunction "1_1") (pintype "passive"))
      (node (ref "C109") (pin "1") (pinfunction "1_1") (pintype "passive"))
      (node (ref "C110") (pin "1") (pinfunction "1_1") (pintype "passive"))
      (node (ref "C111") (pin "1") (pinfunction "1_1") (pintype "passive"))
      (node (ref "C112") (pin "1") (pinfunction "1_1") (pintype "passive"))
      (node (ref "C113") (pin "1") (pinfunction "1_1") (pintype "passive"))
      (node (ref "C114") (pin "1") (pinfunction "1_1") (pintype "passive"))
      (node (ref "C115") (pin "1") (pinfunction "1_1") (pintype "passive"))
      (node (ref "C116") (pin "1") (pinfunction "1_1") (pintype "passive"))
      (node (ref "C117") (pin "1") (pinfunction "1_1") (pintype "passive"))
      (node (ref "C118") (pin "1") (pinfunction "1_1") (pintype "passive"))
      (node (ref "C119") (pin "1") (pinfunction "1_1") (pintype "passive"))
      (node (ref "C120") (pin "1") (pinfunction "1_1") (pintype "passive"))
      (node (ref "C121") (pin "1") (pinfunction "1_1") (pintype "passive"))
      (node (ref "C122") (pin "1") (pinfunction "1_1") (pintype "passive"))
      (node (ref "C123") (pin "1") (pinfunction "1_1") (pintype "passive"))
      (node (ref "C124") (pin "1") (pinfunction "1_1") (pintype "passive"))
      (node (ref "C125") (pin "1") (pinfunction "1_1") (pintype "passive"))
      (node (ref "C126") (pin "1") (pinfunction "1_1") (pintype "passive"))
      (node (ref "C127") (pin "1") (pinfunction "1_1") (pintype "passive"))
      (node (ref "C128") (pin "1") (pinfunction "1_1") (pintype "passive"))
      (node (ref "C129") (pin "1") (pinfunction "1_1") (pintype "passive"))
      (node (ref "C130") (pin "1") (pinfunction "1_1") (pintype "passive"))
      (node (ref "C131") (pin "1") (pinfunction "1_1") (pintype "passive"))
      (node (ref "C132") (pin "1") (pinfunction "1_1") (pintype "passive"))
      (node (ref "C133") (pin "1") (pinfunction "1_1") (pintype "passive"))
      (node (ref "C134") (pin "1") (pinfunction "1_1") (pintype "passive"))
      (node (ref "C135") (pin "1") (pinfunction "1_1") (pintype "passive"))
      (node (ref "C136") (pin "1") (pinfunction "1_1") (pintype "passive"))
      (node (ref "C137") (pin "1") (pinfunction "1_1") (pintype "passive"))
      (node (ref "C138") (pin "1") (pinfunction "1_1") (pintype "passive"))
      (node (ref "C139") (pin "1") (pinfunction "1_1") (pintype "passive"))
      (node (ref "C140") (pin "1") (pinfunction "1_1") (pintype "passive"))
      (node (ref "C141") (pin "1") (pinfunction "1_1") (pintype "passive"))
      (node (ref "C142") (pin "1") (pinfunction "1_1") (pintype "passive"))
      (node (ref "C143") (pin "1") (pinfunction "1_1") (pintype "passive"))
      (node (ref "C144") (pin "1") (pinfunction "1_1") (pintype "passive"))
      (node (ref "C145") (pin "1") (pinfunction "1_1") (pintype "passive"))
      (node (ref "C146") (pin "1") (pinfunction "1_1") (pintype "passive"))
      (node (ref "C147") (pin "1") (pinfunction "1_1") (pintype "passive"))
      (node (ref "C35") (pin "1") (pinfunction "1_1") (pintype "passive"))
      (node (ref "C42") (pin "1") (pinfunction "1_1") (pintype "passive"))
      (node (ref "C43") (pin "1") (pinfunction "1_1") (pintype "passive"))
      (node (ref "C44") (pin "1") (pinfunction "1_1") (pintype "passive"))
      (node (ref "C46") (pin "1") (pinfunction "1_1") (pintype "passive"))
      (node (ref "C47") (pin "1") (pinfunction "1_1") (pintype "passive"))
      (node (ref "C48") (pin "1") (pinfunction "1_1") (pintype "passive"))
      (node (ref "C49") (pin "1") (pinfunction "1_1") (pintype "passive"))
      (node (ref "C53") (pin "1") (pinfunction "1_1") (pintype "passive"))
      (node (ref "C54") (pin "1") (pinfunction "1_1") (pintype "passive"))
      (node (ref "C58") (pin "1") (pinfunction "1_1") (pintype "passive"))
      (node (ref "C59") (pin "1") (pinfunction "1_1") (pintype "passive"))
      (node (ref "C60") (pin "1") (pinfunction "1_1") (pintype "passive"))
      (node (ref "C61") (pin "1") (pinfunction "1_1") (pintype "passive"))
      (node (ref "C62") (pin "1") (pinfunction "1_1") (pintype "passive"))
      (node (ref "C63") (pin "1") (pinfunction "1_1") (pintype "passive"))
      (node (ref "C64") (pin "1") (pinfunction "1_1") (pintype "passive"))
      (node (ref "C65") (pin "1") (pinfunction "1_1") (pintype "passive"))
      (node (ref "C66") (pin "1") (pinfunction "1_1") (pintype "passive"))
      (node (ref "C67") (pin "1") (pinfunction "1_1") (pintype "passive"))
      (node (ref "C68") (pin "1") (pinfunction "1_1") (pintype "passive"))
      (node (ref "C69") (pin "1") (pinfunction "1_1") (pintype "passive"))
      (node (ref "C70") (pin "1") (pinfunction "1_1") (pintype "passive"))
      (node (ref "C71") (pin "1") (pinfunction "1_1") (pintype "passive"))
      (node (ref "C72") (pin "1") (pinfunction "1_1") (pintype "passive"))
      (node (ref "C73") (pin "1") (pinfunction "1_1") (pintype "passive"))
      (node (ref "C74") (pin "1") (pinfunction "1_1") (pintype "passive"))
      (node (ref "C75") (pin "1") (pinfunction "1_1") (pintype "passive"))
      (node (ref "C76") (pin "1") (pinfunction "1_1") (pintype "passive"))
      (node (ref "C77") (pin "1") (pinfunction "1_1") (pintype "passive"))
      (node (ref "C78") (pin "1") (pinfunction "1_1") (pintype "passive"))
      (node (ref "C79") (pin "1") (pinfunction "1_1") (pintype "passive"))
      (node (ref "C80") (pin "1") (pinfunction "1_1") (pintype "passive"))
      (node (ref "C81") (pin "1") (pinfunction "1_1") (pintype "passive"))
      (node (ref "C82") (pin "1") (pinfunction "1_1") (pintype "passive"))
      (node (ref "C83") (pin "1") (pinfunction "1_1") (pintype "passive"))
      (node (ref "C84") (pin "1") (pinfunction "1_1") (pintype "passive"))
      (node (ref "C85") (pin "1") (pinfunction "1_1") (pintype "passive"))
      (node (ref "C86") (pin "1") (pinfunction "1_1") (pintype "passive"))
      (node (ref "C87") (pin "1") (pinfunction "1_1") (pintype "passive"))
      (node (ref "C88") (pin "1") (pinfunction "1_1") (pintype "passive"))
      (node (ref "C89") (pin "1") (pinfunction "1_1") (pintype "passive"))
      (node (ref "C90") (pin "1") (pinfunction "1_1") (pintype "passive"))
      (node (ref "C91") (pin "1") (pinfunction "1_1") (pintype "passive"))
      (node (ref "C92") (pin "1") (pinfunction "1_1") (pintype "passive"))
      (node (ref "C93") (pin "1") (pinfunction "1_1") (pintype "passive"))
      (node (ref "C94") (pin "1") (pinfunction "1_1") (pintype "passive"))
      (node (ref "C98") (pin "1") (pinfunction "1_1") (pintype "passive"))
      (node (ref "DS10") (pin "2") (pinfunction "2_2") (pintype "passive"))
      (node (ref "DS11") (pin "2") (pinfunction "2_2") (pintype "passive"))
      (node (ref "DS12") (pin "2") (pinfunction "2_2") (pintype "passive"))
      (node (ref "DS13") (pin "2") (pinfunction "2_2") (pintype "passive"))
      (node (ref "DS14") (pin "2") (pinfunction "2_2") (pintype "passive"))
      (node (ref "DS15") (pin "2") (pinfunction "2_2") (pintype "passive"))
      (node (ref "DS16") (pin "2") (pinfunction "2_2") (pintype "passive"))
      (node (ref "DS17") (pin "2") (pinfunction "2_2") (pintype "passive"))
      (node (ref "DS18") (pin "2") (pinfunction "2_2") (pintype "passive"))
      (node (ref "DS19") (pin "2") (pinfunction "2_2") (pintype "passive"))
      (node (ref "DS2") (pin "2") (pinfunction "2_2") (pintype "passive"))
      (node (ref "DS20") (pin "2") (pinfunction "2_2") (pintype "passive"))
      (node (ref "DS21") (pin "2") (pinfunction "2_2") (pintype "passive"))
      (node (ref "DS22") (pin "2") (pinfunction "2_2") (pintype "passive"))
      (node (ref "DS23") (pin "2") (pinfunction "2_2") (pintype "passive"))
      (node (ref "DS24") (pin "2") (pinfunction "2_2") (pintype "passive"))
      (node (ref "DS25") (pin "2") (pinfunction "2_2") (pintype "passive"))
      (node (ref "DS26") (pin "2") (pinfunction "2_2") (pintype "passive"))
      (node (ref "DS27") (pin "2") (pinfunction "2_2") (pintype "passive"))
      (node (ref "DS28") (pin "2") (pinfunction "2_2") (pintype "passive"))
      (node (ref "DS29") (pin "2") (pinfunction "2_2") (pintype "passive"))
      (node (ref "DS3") (pin "2") (pinfunction "2_2") (pintype "passive"))
      (node (ref "DS30") (pin "2") (pinfunction "2_2") (pintype "passive"))
      (node (ref "DS31") (pin "2") (pinfunction "2_2") (pintype "passive"))
      (node (ref "DS32") (pin "2") (pinfunction "2_2") (pintype "passive"))
      (node (ref "DS33") (pin "2") (pinfunction "2_2") (pintype "passive"))
      (node (ref "DS34") (pin "2") (pinfunction "2_2") (pintype "passive"))
      (node (ref "DS35") (pin "2") (pinfunction "2_2") (pintype "passive"))
      (node (ref "DS4") (pin "2") (pinfunction "2_2") (pintype "passive"))
      (node (ref "DS5") (pin "2") (pinfunction "2_2") (pintype "passive"))
      (node (ref "DS6") (pin "2") (pinfunction "2_2") (pintype "passive"))
      (node (ref "DS7") (pin "2") (pinfunction "2_2") (pintype "passive"))
      (node (ref "DS8") (pin "2") (pinfunction "2_2") (pintype "passive"))
      (node (ref "DS9") (pin "2") (pinfunction "2_2") (pintype "passive"))
      (node (ref "R101") (pin "2") (pinfunction "2_2") (pintype "passive"))
      (node (ref "R104") (pin "1") (pinfunction "1_1") (pintype "passive"))
      (node (ref "R122") (pin "2") (pinfunction "2_2") (pintype "passive"))
      (node (ref "R145") (pin "2") (pinfunction "2_2") (pintype "passive"))
      (node (ref "R54") (pin "1") (pinfunction "1_1") (pintype "passive"))
      (node (ref "R76") (pin "2") (pinfunction "2_2") (pintype "passive"))
      (node (ref "TVS1") (pin "1") (pinfunction "A_1") (pintype "passive"))
      (node (ref "TVS10") (pin "1") (pinfunction "A_1") (pintype "passive"))
      (node (ref "TVS11") (pin "1") (pinfunction "A_1") (pintype "passive"))
      (node (ref "TVS12") (pin "1") (pinfunction "A_1") (pintype "passive"))
      (node (ref "TVS13") (pin "1") (pinfunction "A_1") (pintype "passive"))
      (node (ref "TVS14") (pin "1") (pinfunction "A_1") (pintype "passive"))
      (node (ref "TVS15") (pin "1") (pinfunction "A_1") (pintype "passive"))
      (node (ref "TVS16") (pin "1") (pinfunction "A_1") (pintype "passive"))
      (node (ref "TVS17") (pin "1") (pinfunction "A_1") (pintype "passive"))
      (node (ref "TVS18") (pin "1") (pinfunction "A_1") (pintype "passive"))
      (node (ref "TVS19") (pin "1") (pinfunction "A_1") (pintype "passive"))
      (node (ref "TVS2") (pin "1") (pinfunction "A_1") (pintype "passive"))
      (node (ref "TVS20") (pin "1") (pinfunction "A_1") (pintype "passive"))
      (node (ref "TVS21") (pin "1") (pinfunction "A_1") (pintype "passive"))
      (node (ref "TVS22") (pin "1") (pinfunction "A_1") (pintype "passive"))
      (node (ref "TVS23") (pin "1") (pinfunction "A_1") (pintype "passive"))
      (node (ref "TVS24") (pin "1") (pinfunction "A_1") (pintype "passive"))
      (node (ref "TVS25") (pin "1") (pinfunction "A_1") (pintype "passive"))
      (node (ref "TVS26") (pin "1") (pinfunction "A_1") (pintype "passive"))
      (node (ref "TVS27") (pin "1") (pinfunction "A_1") (pintype "passive"))
      (node (ref "TVS28") (pin "1") (pinfunction "A_1") (pintype "passive"))
      (node (ref "TVS29") (pin "1") (pinfunction "A_1") (pintype "passive"))
      (node (ref "TVS30") (pin "1") (pinfunction "A_1") (pintype "passive"))
      (node (ref "TVS31") (pin "1") (pinfunction "A_1") (pintype "passive"))
      (node (ref "TVS32") (pin "1") (pinfunction "A_1") (pintype "passive"))
      (node (ref "TVS33") (pin "1") (pinfunction "A_1") (pintype "passive"))
      (node (ref "TVS34") (pin "1") (pinfunction "A_1") (pintype "passive"))
      (node (ref "TVS35") (pin "1") (pinfunction "A_1") (pintype "passive"))
      (node (ref "TVS36") (pin "1") (pinfunction "A_1") (pintype "passive"))
      (node (ref "TVS5") (pin "1") (pinfunction "A_1") (pintype "passive"))
      (node (ref "TVS6") (pin "1") (pinfunction "A_1") (pintype "passive"))
      (node (ref "TVS7") (pin "1") (pinfunction "A_1") (pintype "passive"))
      (node (ref "TVS8") (pin "1") (pinfunction "A_1") (pintype "passive"))
      (node (ref "TVS9") (pin "1") (pinfunction "A_1") (pintype "passive"))
      (node (ref "U11") (pin "4") (pinfunction "V-_4") (pintype "power_in"))
      (node (ref "U12") (pin "4") (pinfunction "V-_4") (pintype "power_in"))
      (node (ref "U13") (pin "20") (pinfunction "AVSS_20") (pintype "passive"))
      (node (ref "U13") (pin "23") (pinfunction "AVSS_23") (pintype "passive"))
      (node (ref "U13") (pin "25") (pinfunction "VREFN_25") (pintype "passive"))
      (node (ref "U13") (pin "31") (pinfunction "RESV1_31") (pintype "passive"))
      (node (ref "U13") (pin "32") (pinfunction "AVSS_32") (pintype "passive"))
      (node (ref "U13") (pin "53") (pinfunction "AVSS1_53") (pintype "passive"))
      (node (ref "U13") (pin "57") (pinfunction "AVSS_57") (pintype "passive"))
      (node (ref "U13") (pin "58") (pinfunction "AVSS_58") (pintype "passive"))
      (node (ref "U14") (pin "4") (pinfunction "V-_4") (pintype "power_in"))
      (node (ref "U8") (pin "4") (pinfunction "V-_4") (pintype "power_in"))
      (node (ref "U9") (pin "20") (pinfunction "AVSS_20") (pintype "passive"))
      (node (ref "U9") (pin "23") (pinfunction "AVSS_23") (pintype "passive"))
      (node (ref "U9") (pin "25") (pinfunction "VREFN_25") (pintype "passive"))
      (node (ref "U9") (pin "31") (pinfunction "RESV1_31") (pintype "passive"))
      (node (ref "U9") (pin "32") (pinfunction "AVSS_32") (pintype "passive"))
      (node (ref "U9") (pin "53") (pinfunction "AVSS1_53") (pintype "passive"))
      (node (ref "U9") (pin "57") (pinfunction "AVSS_57") (pintype "passive"))
      (node (ref "U9") (pin "58") (pinfunction "AVSS_58") (pintype "passive"))
    )
    (net (code "80") (name "DVDD") (class "Default")
      (node (ref "C148") (pin "2") (pinfunction "2_2") (pintype "passive"))
      (node (ref "C149") (pin "2") (pinfunction "2_2") (pintype "passive"))
      (node (ref "C150") (pin "2") (pinfunction "2_2") (pintype "passive"))
      (node (ref "C95") (pin "2") (pinfunction "2_2") (pintype "passive"))
      (node (ref "C96") (pin "2") (pinfunction "2_2") (pintype "passive"))
      (node (ref "C97") (pin "2") (pinfunction "2_2") (pintype "passive"))
      (node (ref "R127") (pin "1") (pinfunction "1_1") (pintype "passive"))
      (node (ref "R83") (pin "1") (pinfunction "1_1") (pintype "passive"))
      (node (ref "U13") (pin "48") (pinfunction "DVDD_48") (pintype "passive"))
      (node (ref "U13") (pin "50") (pinfunction "DVDD_50") (pintype "passive"))
      (node (ref "U13") (pin "52") (pinfunction "CLKSEL_52") (pintype "passive"))
      (node (ref "U9") (pin "48") (pinfunction "DVDD_48") (pintype "passive"))
      (node (ref "U9") (pin "50") (pinfunction "DVDD_50") (pintype "passive"))
      (node (ref "U9") (pin "52") (pinfunction "CLKSEL_52") (pintype "passive"))
    )
    (net (code "81") (name "GND") (class "Default")
      (node (ref "C100") (pin "1") (pinfunction "1_1") (pintype "passive"))
      (node (ref "C101") (pin "1") (pinfunction "1_1") (pintype "passive"))
      (node (ref "C148") (pin "1") (pinfunction "1_1") (pintype "passive"))
      (node (ref "C149") (pin "1") (pinfunction "1_1") (pintype "passive"))
      (node (ref "C150") (pin "1") (pinfunction "1_1") (pintype "passive"))
      (node (ref "C38") (pin "1") (pinfunction "1_1") (pintype "passive"))
      (node (ref "C41") (pin "1") (pinfunction "1_1") (pintype "passive"))
      (node (ref "C95") (pin "1") (pinfunction "1_1") (pintype "passive"))
      (node (ref "C96") (pin "1") (pinfunction "1_1") (pintype "passive"))
      (node (ref "C97") (pin "1") (pinfunction "1_1") (pintype "passive"))
      (node (ref "R101") (pin "1") (pinfunction "1_1") (pintype "passive"))
      (node (ref "R145") (pin "1") (pinfunction "1_1") (pintype "passive"))
      (node (ref "U13") (pin "33") (pinfunction "DGND_33") (pintype "passive"))
      (node (ref "U13") (pin "37") (pinfunction "CLK_37") (pintype "passive"))
      (node (ref "U13") (pin "38") (pinfunction "START_38") (pintype "passive"))
      (node (ref "U13") (pin "41") (pinfunction "DAISY_IN_41") (pintype "passive"))
      (node (ref "U13") (pin "49") (pinfunction "DGND_49") (pintype "passive"))
      (node (ref "U13") (pin "51") (pinfunction "DGND_51") (pintype "passive"))
      (node (ref "U9") (pin "33") (pinfunction "DGND_33") (pintype "passive"))
      (node (ref "U9") (pin "37") (pinfunction "CLK_37") (pintype "passive"))
      (node (ref "U9") (pin "38") (pinfunction "START_38") (pintype "passive"))
      (node (ref "U9") (pin "41") (pinfunction "DAISY_IN_41") (pintype "passive"))
      (node (ref "U9") (pin "49") (pinfunction "DGND_49") (pintype "passive"))
      (node (ref "U9") (pin "51") (pinfunction "DGND_51") (pintype "passive"))
    )
    (net (code "82") (name "Net-(C42-Pad2)") (class "Default")
      (node (ref "C42") (pin "2") (pinfunction "2_2") (pintype "passive"))
      (node (ref "DS2") (pin "1") (pinfunction "1_1") (pintype "passive"))
      (node (ref "R60") (pin "2") (pinfunction "2_2") (pintype "passive"))
      (node (ref "R61") (pin "1") (pinfunction "1_1") (pintype "passive"))
    )
    (net (code "83") (name "Net-(C44-Pad2)") (class "Default")
      (node (ref "C44") (pin "2") (pinfunction "2_2") (pintype "passive"))
      (node (ref "DS3") (pin "1") (pinfunction "1_1") (pintype "passive"))
      (node (ref "R62") (pin "2") (pinfunction "2_2") (pintype "passive"))
      (node (ref "R63") (pin "1") (pinfunction "1_1") (pintype "passive"))
    )
    (net (code "84") (name "Net-(C47-Pad2)") (class "Default")
      (node (ref "C47") (pin "2") (pinfunction "2_2") (pintype "passive"))
      (node (ref "DS4") (pin "1") (pinfunction "1_1") (pintype "passive"))
      (node (ref "R65") (pin "2") (pinfunction "2_2") (pintype "passive"))
      (node (ref "R66") (pin "1") (pinfunction "1_1") (pintype "passive"))
    )
    (net (code "85") (name "Net-(C49-Pad2)") (class "Default")
      (node (ref "C49") (pin "2") (pinfunction "2_2") (pintype "passive"))
      (node (ref "DS5") (pin "1") (pinfunction "1_1") (pintype "passive"))
      (node (ref "R67") (pin "2") (pinfunction "2_2") (pintype "passive"))
      (node (ref "R68") (pin "1") (pinfunction "1_1") (pintype "passive"))
    )
    (net (code "86") (name "Net-(C54-Pad2)") (class "Default")
      (node (ref "C54") (pin "2") (pinfunction "2_2") (pintype "passive"))
      (node (ref "DS6") (pin "1") (pinfunction "1_1") (pintype "passive"))
      (node (ref "R69") (pin "2") (pinfunction "2_2") (pintype "passive"))
      (node (ref "R70") (pin "1") (pinfunction "1_1") (pintype "passive"))
    )
    (net (code "87") (name "Net-(C59-Pad2)") (class "Default")
      (node (ref "C59") (pin "2") (pinfunction "2_2") (pintype "passive"))
      (node (ref "DS7") (pin "1") (pinfunction "1_1") (pintype "passive"))
      (node (ref "R72") (pin "2") (pinfunction "2_2") (pintype "passive"))
      (node (ref "R73") (pin "1") (pinfunction "1_1") (pintype "passive"))
    )
    (net (code "88") (name "Net-(C61-Pad2)") (class "Default")
      (node (ref "C61") (pin "2") (pinfunction "2_2") (pintype "passive"))
      (node (ref "DS8") (pin "1") (pinfunction "1_1") (pintype "passive"))
      (node (ref "R74") (pin "2") (pinfunction "2_2") (pintype "passive"))
      (node (ref "R75") (pin "1") (pinfunction "1_1") (pintype "passive"))
    )
    (net (code "89") (name "Net-(C63-Pad2)") (class "Default")
      (node (ref "C63") (pin "2") (pinfunction "2_2") (pintype "passive"))
      (node (ref "DS9") (pin "1") (pinfunction "1_1") (pintype "passive"))
      (node (ref "R77") (pin "2") (pinfunction "2_2") (pintype "passive"))
      (node (ref "R80") (pin "1") (pinfunction "1_1") (pintype "passive"))
    )
    (net (code "90") (name "Net-(C65-Pad2)") (class "Default")
      (node (ref "C65") (pin "2") (pinfunction "2_2") (pintype "passive"))
      (node (ref "DS10") (pin "1") (pinfunction "1_1") (pintype "passive"))
      (node (ref "R81") (pin "2") (pinfunction "2_2") (pintype "passive"))
      (node (ref "R82") (pin "1") (pinfunction "1_1") (pintype "passive"))
    )
    (net (code "91") (name "Net-(C67-Pad2)") (class "Default")
      (node (ref "C67") (pin "2") (pinfunction "2_2") (pintype "passive"))
      (node (ref "DS11") (pin "1") (pinfunction "1_1") (pintype "passive"))
      (node (ref "R84") (pin "2") (pinfunction "2_2") (pintype "passive"))
      (node (ref "R85") (pin "1") (pinfunction "1_1") (pintype "passive"))
    )
    (net (code "92") (name "Net-(C69-Pad2)") (class "Default")
      (node (ref "C69") (pin "2") (pinfunction "2_2") (pintype "passive"))
      (node (ref "DS12") (pin "1") (pinfunction "1_1") (pintype "passive"))
      (node (ref "R86") (pin "2") (pinfunction "2_2") (pintype "passive"))
      (node (ref "R87") (pin "1") (pinfunction "1_1") (pintype "passive"))
    )
    (net (code "93") (name "Net-(C72-Pad2)") (class "Default")
      (node (ref "C72") (pin "2") (pinfunction "2_2") (pintype "passive"))
      (node (ref "DS13") (pin "1") (pinfunction "1_1") (pintype "passive"))
      (node (ref "R88") (pin "2") (pinfunction "2_2") (pintype "passive"))
      (node (ref "R89") (pin "1") (pinfunction "1_1") (pintype "passive"))
    )
    (net (code "94") (name "Net-(C74-Pad2)") (class "Default")
      (node (ref "C74") (pin "2") (pinfunction "2_2") (pintype "passive"))
      (node (ref "DS14") (pin "1") (pinfunction "1_1") (pintype "passive"))
      (node (ref "R90") (pin "2") (pinfunction "2_2") (pintype "passive"))
      (node (ref "R91") (pin "1") (pinfunction "1_1") (pintype "passive"))
    )
    (net (code "95") (name "Net-(C82-Pad2)") (class "Default")
      (node (ref "C82") (pin "2") (pinfunction "2_2") (pintype "passive"))
      (node (ref "DS15") (pin "1") (pinfunction "1_1") (pintype "passive"))
      (node (ref "R93") (pin "2") (pinfunction "2_2") (pintype "passive"))
      (node (ref "R94") (pin "1") (pinfunction "1_1") (pintype "passive"))
    )
    (net (code "96") (name "Net-(C84-Pad2)") (class "Default")
      (node (ref "C84") (pin "2") (pinfunction "2_2") (pintype "passive"))
      (node (ref "DS16") (pin "1") (pinfunction "1_1") (pintype "passive"))
      (node (ref "R95") (pin "2") (pinfunction "2_2") (pintype "passive"))
      (node (ref "R96") (pin "1") (pinfunction "1_1") (pintype "passive"))
    )
    (net (code "97") (name "Net-(C86-Pad2)") (class "Default")
      (node (ref "C86") (pin "2") (pinfunction "2_2") (pintype "passive"))
      (node (ref "DS17") (pin "1") (pinfunction "1_1") (pintype "passive"))
      (node (ref "R97") (pin "2") (pinfunction "2_2") (pintype "passive"))
      (node (ref "R98") (pin "1") (pinfunction "1_1") (pintype "passive"))
    )
    (net (code "98") (name "Net-(C88-Pad2)") (class "Default")
      (node (ref "C88") (pin "2") (pinfunction "2_2") (pintype "passive"))
      (node (ref "DS18") (pin "1") (pinfunction "1_1") (pintype "passive"))
      (node (ref "R100") (pin "1") (pinfunction "1_1") (pintype "passive"))
      (node (ref "R99") (pin "2") (pinfunction "2_2") (pintype "passive"))
    )
    (net (code "99") (name "Net-(C102-Pad2)") (class "Default")
      (node (ref "C102") (pin "2") (pinfunction "2_2") (pintype "passive"))
      (node (ref "DS19") (pin "1") (pinfunction "1_1") (pintype "passive"))
      (node (ref "R106") (pin "2") (pinfunction "2_2") (pintype "passive"))
      (node (ref "R107") (pin "1") (pinfunction "1_1") (pintype "passive"))
    )
    (net (code "100") (name "Net-(C104-Pad2)") (class "Default")
      (node (ref "C104") (pin "2") (pinfunction "2_2") (pintype "passive"))
      (node (ref "DS20") (pin "1") (pinfunction "1_1") (pintype "passive"))
      (node (ref "R108") (pin "2") (pinfunction "2_2") (pintype "passive"))
      (node (ref "R109") (pin "1") (pinfunction "1_1") (pintype "passive"))
    )
    (net (code "101") (name "Net-(C106-Pad2)") (class "Default")
      (node (ref "C106") (pin "2") (pinfunction "2_2") (pintype "passive"))
      (node (ref "DS21") (pin "1") (pinfunction "1_1") (pintype "passive"))
      (node (ref "R111") (pin "2") (pinfunction "2_2") (pintype "passive"))
      (node (ref "R112") (pin "1") (pinfunction "1_1") (pintype "passive"))
    )
    (net (code "102") (name "Net-(C108-Pad2)") (class "Default")
      (node (ref "C108") (pin "2") (pinfunction "2_2") (pintype "passive"))
      (node (ref "DS22") (pin "1") (pinfunction "1_1") (pintype "passive"))
      (node (ref "R113") (pin "2") (pinfunction "2_2") (pintype "passive"))
      (node (ref "R114") (pin "1") (pinfunction "1_1") (pintype "passive"))
    )
    (net (code "103") (name "Net-(C110-Pad2)") (class "Default")
      (node (ref "C110") (pin "2") (pinfunction "2_2") (pintype "passive"))
      (node (ref "DS23") (pin "1") (pinfunction "1_1") (pintype "passive"))
      (node (ref "R115") (pin "2") (pinfunction "2_2") (pintype "passive"))
      (node (ref "R116") (pin "1") (pinfunction "1_1") (pintype "passive"))
    )
    (net (code "104") (name "Net-(C112-Pad2)") (class "Default")
      (node (ref "C112") (pin "2") (pinfunction "2_2") (pintype "passive"))
      (node (ref "DS24") (pin "1") (pinfunction "1_1") (pintype "passive"))
      (node (ref "R118") (pin "2") (pinfunction "2_2") (pintype "passive"))
      (node (ref "R119") (pin "1") (pinfunction "1_1") (pintype "passive"))
    )
    (net (code "105") (name "Net-(C114-Pad2)") (class "Default")
      (node (ref "C114") (pin "2") (pinfunction "2_2") (pintype "passive"))
      (node (ref "DS25") (pin "1") (pinfunction "1_1") (pintype "passive"))
      (node (ref "R120") (pin "2") (pinfunction "2_2") (pintype "passive"))
      (node (ref "R121") (pin "1") (pinfunction "1_1") (pintype "passive"))
    )
    (net (code "106") (name "Net-(C116-Pad2)") (class "Default")
      (node (ref "C116") (pin "2") (pinfunction "2_2") (pintype "passive"))
      (node (ref "DS26") (pin "1") (pinfunction "1_1") (pintype "passive"))
      (node (ref "R123") (pin "2") (pinfunction "2_2") (pintype "passive"))
      (node (ref "R124") (pin "1") (pinfunction "1_1") (pintype "passive"))
    )
    (net (code "107") (name "Net-(C118-Pad2)") (class "Default")
      (node (ref "C118") (pin "2") (pinfunction "2_2") (pintype "passive"))
      (node (ref "DS27") (pin "1") (pinfunction "1_1") (pintype "passive"))
      (node (ref "R125") (pin "2") (pinfunction "2_2") (pintype "passive"))
      (node (ref "R126") (pin "1") (pinfunction "1_1") (pintype "passive"))
    )
    (net (code "108") (name "Net-(C120-Pad2)") (class "Default")
      (node (ref "C120") (pin "2") (pinfunction "2_2") (pintype "passive"))
      (node (ref "DS28") (pin "1") (pinfunction "1_1") (pintype "passive"))
      (node (ref "R128") (pin "2") (pinfunction "2_2") (pintype "passive"))
      (node (ref "R129") (pin "1") (pinfunction "1_1") (pintype "passive"))
    )
    (net (code "109") (name "Net-(C122-Pad2)") (class "Default")
      (node (ref "C122") (pin "2") (pinfunction "2_2") (pintype "passive"))
      (node (ref "DS29") (pin "1") (pinfunction "1_1") (pintype "passive"))
      (node (ref "R130") (pin "2") (pinfunction "2_2") (pintype "passive"))
      (node (ref "R131") (pin "1") (pinfunction "1_1") (pintype "passive"))
    )
    (net (code "110") (name "Net-(C125-Pad2)") (class "Default")
      (node (ref "C125") (pin "2") (pinfunction "2_2") (pintype "passive"))
      (node (ref "DS30") (pin "1") (pinfunction "1_1") (pintype "passive"))
      (node (ref "R132") (pin "2") (pinfunction "2_2") (pintype "passive"))
      (node (ref "R133") (pin "1") (pinfunction "1_1") (pintype "passive"))
    )
    (net (code "111") (name "Net-(C127-Pad2)") (class "Default")
      (node (ref "C127") (pin "2") (pinfunction "2_2") (pintype "passive"))
      (node (ref "DS31") (pin "1") (pinfunction "1_1") (pintype "passive"))
      (node (ref "R134") (pin "2") (pinfunction "2_2") (pintype "passive"))
      (node (ref "R135") (pin "1") (pinfunction "1_1") (pintype "passive"))
    )
    (net (code "112") (name "Net-(C135-Pad2)") (class "Default")
      (node (ref "C135") (pin "2") (pinfunction "2_2") (pintype "passive"))
      (node (ref "DS32") (pin "1") (pinfunction "1_1") (pintype "passive"))
      (node (ref "R137") (pin "2") (pinfunction "2_2") (pintype "passive"))
      (node (ref "R138") (pin "1") (pinfunction "1_1") (pintype "passive"))
    )
    (net (code "113") (name "Net-(C137-Pad2)") (class "Default")
      (node (ref "C137") (pin "2") (pinfunction "2_2") (pintype "passive"))
      (node (ref "DS33") (pin "1") (pinfunction "1_1") (pintype "passive"))
      (node (ref "R139") (pin "2") (pinfunction "2_2") (pintype "passive"))
      (node (ref "R140") (pin "1") (pinfunction "1_1") (pintype "passive"))
    )
    (net (code "114") (name "Net-(C139-Pad2)") (class "Default")
      (node (ref "C139") (pin "2") (pinfunction "2_2") (pintype "passive"))
      (node (ref "DS34") (pin "1") (pinfunction "1_1") (pintype "passive"))
      (node (ref "R141") (pin "2") (pinfunction "2_2") (pintype "passive"))
      (node (ref "R142") (pin "1") (pinfunction "1_1") (pintype "passive"))
    )
    (net (code "115") (name "Net-(C141-Pad2)") (class "Default")
      (node (ref "C141") (pin "2") (pinfunction "2_2") (pintype "passive"))
      (node (ref "DS35") (pin "1") (pinfunction "1_1") (pintype "passive"))
      (node (ref "R143") (pin "2") (pinfunction "2_2") (pintype "passive"))
      (node (ref "R144") (pin "1") (pinfunction "1_1") (pintype "passive"))
    )
    (net (code "116") (name "Net-(P11-Pad1)") (class "Default")
      (node (ref "P11") (pin "1") (pinfunction "1_1") (pintype "passive"))
      (node (ref "R52") (pin "1") (pinfunction "1_1") (pintype "passive"))
    )
    (net (code "117") (name "Net-(P14-Pad1)") (class "Default")
      (node (ref "P14") (pin "1") (pinfunction "1_1") (pintype "passive"))
      (node (ref "P15") (pin "3") (pinfunction "3_3") (pintype "passive"))
    )
    (net (code "118") (name "Net-(P15-Pad2)") (class "Default")
      (node (ref "P15") (pin "2") (pinfunction "2_2") (pintype "passive"))
      (node (ref "R92") (pin "1") (pinfunction "1_1") (pintype "passive"))
    )
    (net (code "119") (name "Net-(P17-Pad1)") (class "Default")
      (node (ref "P17") (pin "1") (pinfunction "1_1") (pintype "passive"))
      (node (ref "R102") (pin "1") (pinfunction "1_1") (pintype "passive"))
    )
    (net (code "120") (name "Net-(P20-Pad1)") (class "Default")
      (node (ref "P20") (pin "1") (pinfunction "1_1") (pintype "passive"))
      (node (ref "P21") (pin "3") (pinfunction "3_3") (pintype "passive"))
    )
    (net (code "121") (name "Net-(P21-Pad2)") (class "Default")
      (node (ref "P21") (pin "2") (pinfunction "2_2") (pintype "passive"))
      (node (ref "R136") (pin "1") (pinfunction "1_1") (pintype "passive"))
    )
    (net (code "122") (name "Net-(TVS5-B)") (class "Default")
      (node (ref "C48") (pin "2") (pinfunction "2_2") (pintype "passive"))
      (node (ref "P11") (pin "2") (pinfunction "2_2") (pintype "passive"))
      (node (ref "R64") (pin "2") (pinfunction "2_2") (pintype "passive"))
      (node (ref "R66") (pin "2") (pinfunction "2_2") (pintype "passive"))
      (node (ref "TVS5") (pin "2") (pinfunction "B_2") (pintype "passive"))
    )
    (net (code "123") (name "Net-(TVS22-B)") (class "Default")
      (node (ref "C107") (pin "2") (pinfunction "2_2") (pintype "passive"))
      (node (ref "P17") (pin "2") (pinfunction "2_2") (pintype "passive"))
      (node (ref "R110") (pin "2") (pinfunction "2_2") (pintype "passive"))
      (node (ref "R112") (pin "2") (pinfunction "2_2") (pintype "passive"))
      (node (ref "TVS22") (pin "2") (pinfunction "B_2") (pintype "passive"))
    )
    (net (code "124") (name "Net-(U8A-IN1+)") (class "Default")
      (node (ref "R52") (pin "2") (pinfunction "2_2") (pintype "passive"))
      (node (ref "U8") (pin "3") (pinfunction "IN1+_3") (pintype "input"))
    )
    (net (code "125") (name "Net-(U8B-IN2+)") (class "Default")
      (node (ref "R71") (pin "2") (pinfunction "2_2") (pintype "passive"))
      (node (ref "R76") (pin "1") (pinfunction "1_1") (pintype "passive"))
      (node (ref "U8") (pin "5") (pinfunction "IN2+_5") (pintype "input"))
    )
    (net (code "126") (name "Net-(U8B-IN2-)") (class "Default")
      (node (ref "P13") (pin "2") (pinfunction "2_2") (pintype "passive"))
      (node (ref "U8") (pin "6") (pinfunction "IN2-_6") (pintype "input"))
      (node (ref "U8") (pin "7") (pinfunction "OUT2_7") (pintype "output"))
    )
    (net (code "127") (name "Net-(U9-BIASIN)") (class "Default")
      (node (ref "P12") (pin "3") (pinfunction "3_3") (pintype "passive"))
      (node (ref "P13") (pin "3") (pinfunction "3_3") (pintype "passive"))
      (node (ref "U9") (pin "62") (pinfunction "BIASIN_62") (pintype "passive"))
    )
    (net (code "128") (name "Net-(U9-BIASINV)") (class "Default")
      (node (ref "C37") (pin "1") (pinfunction "1_1") (pintype "passive"))
      (node (ref "R55") (pin "1") (pinfunction "1_1") (pintype "passive"))
      (node (ref "U9") (pin "61") (pinfunction "BIASINV_61") (pintype "passive"))
    )
    (net (code "129") (name "Net-(U9-BIASOUT)") (class "Default")
      (node (ref "C37") (pin "2") (pinfunction "2_2") (pintype "passive"))
      (node (ref "P12") (pin "2") (pinfunction "2_2") (pintype "passive"))
      (node (ref "R55") (pin "2") (pinfunction "2_2") (pintype "passive"))
      (node (ref "R64") (pin "1") (pinfunction "1_1") (pintype "passive"))
      (node (ref "U9") (pin "63") (pinfunction "BIASOUT_63") (pintype "passive"))
    )
    (net (code "130") (name "Net-(U9-BIASREF)") (class "Default")
      (node (ref "R53") (pin "2") (pinfunction "2_2") (pintype "passive"))
      (node (ref "R54") (pin "2") (pinfunction "2_2") (pintype "passive"))
      (node (ref "R54") (pin "3") (pinfunction "3_3") (pintype "passive"))
      (node (ref "U9") (pin "60") (pinfunction "BIASREF_60") (pintype "passive"))
    )
    (net (code "131") (name "Net-(U9-SRB1)") (class "Default")
      (node (ref "P14") (pin "2") (pinfunction "2_2") (pintype "passive"))
      (node (ref "U9") (pin "17") (pinfunction "SRB1_17") (pintype "passive"))
    )
    (net (code "132") (name "Net-(U9-SRB2)") (class "Default")
      (node (ref "P15") (pin "1") (pinfunction "1_1") (pintype "passive"))
      (node (ref "U9") (pin "18") (pinfunction "SRB2_18") (pintype "passive"))
    )
    (net (code "133") (name "Net-(U9-VCAP1)") (class "Default")
      (node (ref "C79") (pin "2") (pinfunction "2_2") (pintype "passive"))
      (node (ref "C80") (pin "2") (pinfunction "2_2") (pintype "passive"))
      (node (ref "U9") (pin "28") (pinfunction "VCAP1_28") (pintype "passive"))
    )
    (net (code "134") (name "Net-(U9-VCAP2)") (class "Default")
      (node (ref "C81") (pin "2") (pinfunction "2_2") (pintype "passive"))
      (node (ref "U9") (pin "30") (pinfunction "VCAP2_30") (pintype "passive"))
    )
    (net (code "135") (name "Net-(U9-VCAP3)") (class "Default")
      (node (ref "C38") (pin "2") (pinfunction "2_2") (pintype "passive"))
      (node (ref "C41") (pin "2") (pinfunction "2_2") (pintype "passive"))
      (node (ref "U9") (pin "55") (pinfunction "VCAP3_55") (pintype "passive"))
    )
    (net (code "136") (name "Net-(U9-VCAP4)") (class "Default")
      (node (ref "C78") (pin "2") (pinfunction "2_2") (pintype "passive"))
      (node (ref "U9") (pin "26") (pinfunction "VCAP4_26") (pintype "passive"))
    )
    (net (code "137") (name "Net-(U9-VREFP)") (class "Default")
      (node (ref "C76") (pin "2") (pinfunction "2_2") (pintype "passive"))
      (node (ref "C77") (pin "2") (pinfunction "2_2") (pintype "passive"))
      (node (ref "U9") (pin "24") (pinfunction "VREFP_24") (pintype "passive"))
    )
    (net (code "138") (name "Net-(U9-~{PWDN})") (class "Default")
      (node (ref "R83") (pin "2") (pinfunction "2_2") (pintype "passive"))
      (node (ref "U9") (pin "35") (pinfunction "~{PWDN}_35") (pintype "passive"))
      (node (ref "U9") (pin "36") (pinfunction "~{RESET}_36") (pintype "passive"))
    )
    (net (code "139") (name "Net-(U11A-IN1+)") (class "Default")
      (node (ref "R92") (pin "2") (pinfunction "2_2") (pintype "passive"))
      (node (ref "U11") (pin "3") (pinfunction "IN1+_3") (pintype "input"))
    )
    (net (code "140") (name "Net-(U11A-IN1-)") (class "Default")
      (node (ref "P14") (pin "3") (pinfunction "3_3") (pintype "passive"))
      (node (ref "U11") (pin "1") (pinfunction "OUT1_1") (pintype "output"))
      (node (ref "U11") (pin "2") (pinfunction "IN1-_2") (pintype "input"))
    )
    (net (code "141") (name "Net-(U11B-IN2+)") (class "Default")
      (node (ref "R117") (pin "2") (pinfunction "2_2") (pintype "passive"))
      (node (ref "R122") (pin "1") (pinfunction "1_1") (pintype "passive"))
      (node (ref "U11") (pin "5") (pinfunction "IN2+_5") (pintype "input"))
    )
    (net (code "142") (name "Net-(U11B-IN2-)") (class "Default")
      (node (ref "P19") (pin "2") (pinfunction "2_2") (pintype "passive"))
      (node (ref "U11") (pin "6") (pinfunction "IN2-_6") (pintype "input"))
      (node (ref "U11") (pin "7") (pinfunction "OUT2_7") (pintype "output"))
    )
    (net (code "143") (name "Net-(U12A-IN1+)") (class "Default")
      (node (ref "R102") (pin "2") (pinfunction "2_2") (pintype "passive"))
      (node (ref "U12") (pin "3") (pinfunction "IN1+_3") (pintype "input"))
    )
    (net (code "144") (name "Net-(U13-BIASIN)") (class "Default")
      (node (ref "P18") (pin "3") (pinfunction "3_3") (pintype "passive"))
      (node (ref "P19") (pin "3") (pinfunction "3_3") (pintype "passive"))
      (node (ref "U13") (pin "62") (pinfunction "BIASIN_62") (pintype "passive"))
    )
    (net (code "145") (name "Net-(U13-BIASINV)") (class "Default")
      (node (ref "C99") (pin "1") (pinfunction "1_1") (pintype "passive"))
      (node (ref "R105") (pin "1") (pinfunction "1_1") (pintype "passive"))
      (node (ref "U13") (pin "61") (pinfunction "BIASINV_61") (pintype "passive"))
    )
    (net (code "146") (name "Net-(U13-BIASOUT)") (class "Default")
      (node (ref "C99") (pin "2") (pinfunction "2_2") (pintype "passive"))
      (node (ref "P18") (pin "2") (pinfunction "2_2") (pintype "passive"))
      (node (ref "R105") (pin "2") (pinfunction "2_2") (pintype "passive"))
      (node (ref "R110") (pin "1") (pinfunction "1_1") (pintype "passive"))
      (node (ref "U13") (pin "63") (pinfunction "BIASOUT_63") (pintype "passive"))
    )
    (net (code "147") (name "Net-(U13-BIASREF)") (class "Default")
      (node (ref "R103") (pin "2") (pinfunction "2_2") (pintype "passive"))
      (node (ref "R104") (pin "2") (pinfunction "2_2") (pintype "passive"))
      (node (ref "R104") (pin "3") (pinfunction "3_3") (pintype "passive"))
      (node (ref "U13") (pin "60") (pinfunction "BIASREF_60") (pintype "passive"))
    )
    (net (code "148") (name "Net-(U13-SRB1)") (class "Default")
      (node (ref "P20") (pin "2") (pinfunction "2_2") (pintype "passive"))
      (node (ref "U13") (pin "17") (pinfunction "SRB1_17") (pintype "passive"))
    )
    (net (code "149") (name "Net-(U13-SRB2)") (class "Default")
      (node (ref "P21") (pin "1") (pinfunction "1_1") (pintype "passive"))
      (node (ref "U13") (pin "18") (pinfunction "SRB2_18") (pintype "passive"))
    )
    (net (code "150") (name "Net-(U13-VCAP1)") (class "Default")
      (node (ref "C132") (pin "2") (pinfunction "2_2") (pintype "passive"))
      (node (ref "C133") (pin "2") (pinfunction "2_2") (pintype "passive"))
      (node (ref "U13") (pin "28") (pinfunction "VCAP1_28") (pintype "passive"))
    )
    (net (code "151") (name "Net-(U13-VCAP2)") (class "Default")
      (node (ref "C134") (pin "2") (pinfunction "2_2") (pintype "passive"))
      (node (ref "U13") (pin "30") (pinfunction "VCAP2_30") (pintype "passive"))
    )
    (net (code "152") (name "Net-(U13-VCAP3)") (class "Default")
      (node (ref "C100") (pin "2") (pinfunction "2_2") (pintype "passive"))
      (node (ref "C101") (pin "2") (pinfunction "2_2") (pintype "passive"))
      (node (ref "U13") (pin "55") (pinfunction "VCAP3_55") (pintype "passive"))
    )
    (net (code "153") (name "Net-(U13-VCAP4)") (class "Default")
      (node (ref "C131") (pin "2") (pinfunction "2_2") (pintype "passive"))
      (node (ref "U13") (pin "26") (pinfunction "VCAP4_26") (pintype "passive"))
    )
    (net (code "154") (name "Net-(U13-VREFP)") (class "Default")
      (node (ref "C129") (pin "2") (pinfunction "2_2") (pintype "passive"))
      (node (ref "C130") (pin "2") (pinfunction "2_2") (pintype "passive"))
      (node (ref "U13") (pin "24") (pinfunction "VREFP_24") (pintype "passive"))
    )
    (net (code "155") (name "Net-(U13-~{PWDN})") (class "Default")
      (node (ref "R127") (pin "2") (pinfunction "2_2") (pintype "passive"))
      (node (ref "U13") (pin "35") (pinfunction "~{PWDN}_35") (pintype "passive"))
      (node (ref "U13") (pin "36") (pinfunction "~{RESET}_36") (pintype "passive"))
    )
    (net (code "156") (name "Net-(U14A-IN1+)") (class "Default")
      (node (ref "R136") (pin "2") (pinfunction "2_2") (pintype "passive"))
      (node (ref "U14") (pin "3") (pinfunction "IN1+_3") (pintype "input"))
    )
    (net (code "157") (name "Net-(U14A-IN1-)") (class "Default")
      (node (ref "P20") (pin "3") (pinfunction "3_3") (pintype "passive"))
      (node (ref "U14") (pin "1") (pinfunction "OUT1_1") (pintype "output"))
      (node (ref "U14") (pin "2") (pinfunction "IN1-_2") (pintype "input"))
    )
    (net (code "158") (name "unconnected-(P16-Pad18)") (class "Default")
      (node (ref "P16") (pin "18") (pinfunction "18_18") (pintype "passive"))
    )
    (net (code "159") (name "unconnected-(P29-Pad18)") (class "Default")
      (node (ref "P29") (pin "18") (pinfunction "18_18") (pintype "passive"))
    )
    (net (code "160") (name "unconnected-(U9-GPIO1-Pad42)") (class "Default")
      (node (ref "U9") (pin "42") (pinfunction "GPIO1_42") (pintype "passive"))
    )
    (net (code "161") (name "unconnected-(U9-GPIO2-Pad44)") (class "Default")
      (node (ref "U9") (pin "44") (pinfunction "GPIO2_44") (pintype "passive"))
    )
    (net (code "162") (name "unconnected-(U9-GPIO3-Pad45)") (class "Default")
      (node (ref "U9") (pin "45") (pinfunction "GPIO3_45") (pintype "passive"))
    )
    (net (code "163") (name "unconnected-(U9-GPIO4-Pad46)") (class "Default")
      (node (ref "U9") (pin "46") (pinfunction "GPIO4_46") (pintype "passive"))
    )
    (net (code "164") (name "unconnected-(U9-NC-Pad27)") (class "Default")
      (node (ref "U9") (pin "27") (pinfunction "NC_27") (pintype "passive"))
    )
    (net (code "165") (name "unconnected-(U9-NC-Pad29)") (class "Default")
      (node (ref "U9") (pin "29") (pinfunction "NC_29") (pintype "passive"))
    )
    (net (code "166") (name "unconnected-(U9-RESERVED-Pad64)") (class "Default")
      (node (ref "U9") (pin "64") (pinfunction "RESERVED_64") (pintype "passive"))
    )
    (net (code "167") (name "unconnected-(U13-GPIO1-Pad42)") (class "Default")
      (node (ref "U13") (pin "42") (pinfunction "GPIO1_42") (pintype "passive"))
    )
    (net (code "168") (name "unconnected-(U13-GPIO2-Pad44)") (class "Default")
      (node (ref "U13") (pin "44") (pinfunction "GPIO2_44") (pintype "passive"))
    )
    (net (code "169") (name "unconnected-(U13-GPIO3-Pad45)") (class "Default")
      (node (ref "U13") (pin "45") (pinfunction "GPIO3_45") (pintype "passive"))
    )
    (net (code "170") (name "unconnected-(U13-GPIO4-Pad46)") (class "Default")
      (node (ref "U13") (pin "46") (pinfunction "GPIO4_46") (pintype "passive"))
    )
    (net (code "171") (name "unconnected-(U13-NC-Pad27)") (class "Default")
      (node (ref "U13") (pin "27") (pinfunction "NC_27") (pintype "passive"))
    )
    (net (code "172") (name "unconnected-(U13-NC-Pad29)") (class "Default")
      (node (ref "U13") (pin "29") (pinfunction "NC_29") (pintype "passive"))
    )
    (net (code "173") (name "unconnected-(U13-RESERVED-Pad64)") (class "Default")
      (node (ref "U13") (pin "64") (pinfunction "RESERVED_64") (pintype "passive"))
    )
  )
)
